# vr42-revB-kbd.net
KiCad netlist of a schematic drawn in EAGLE
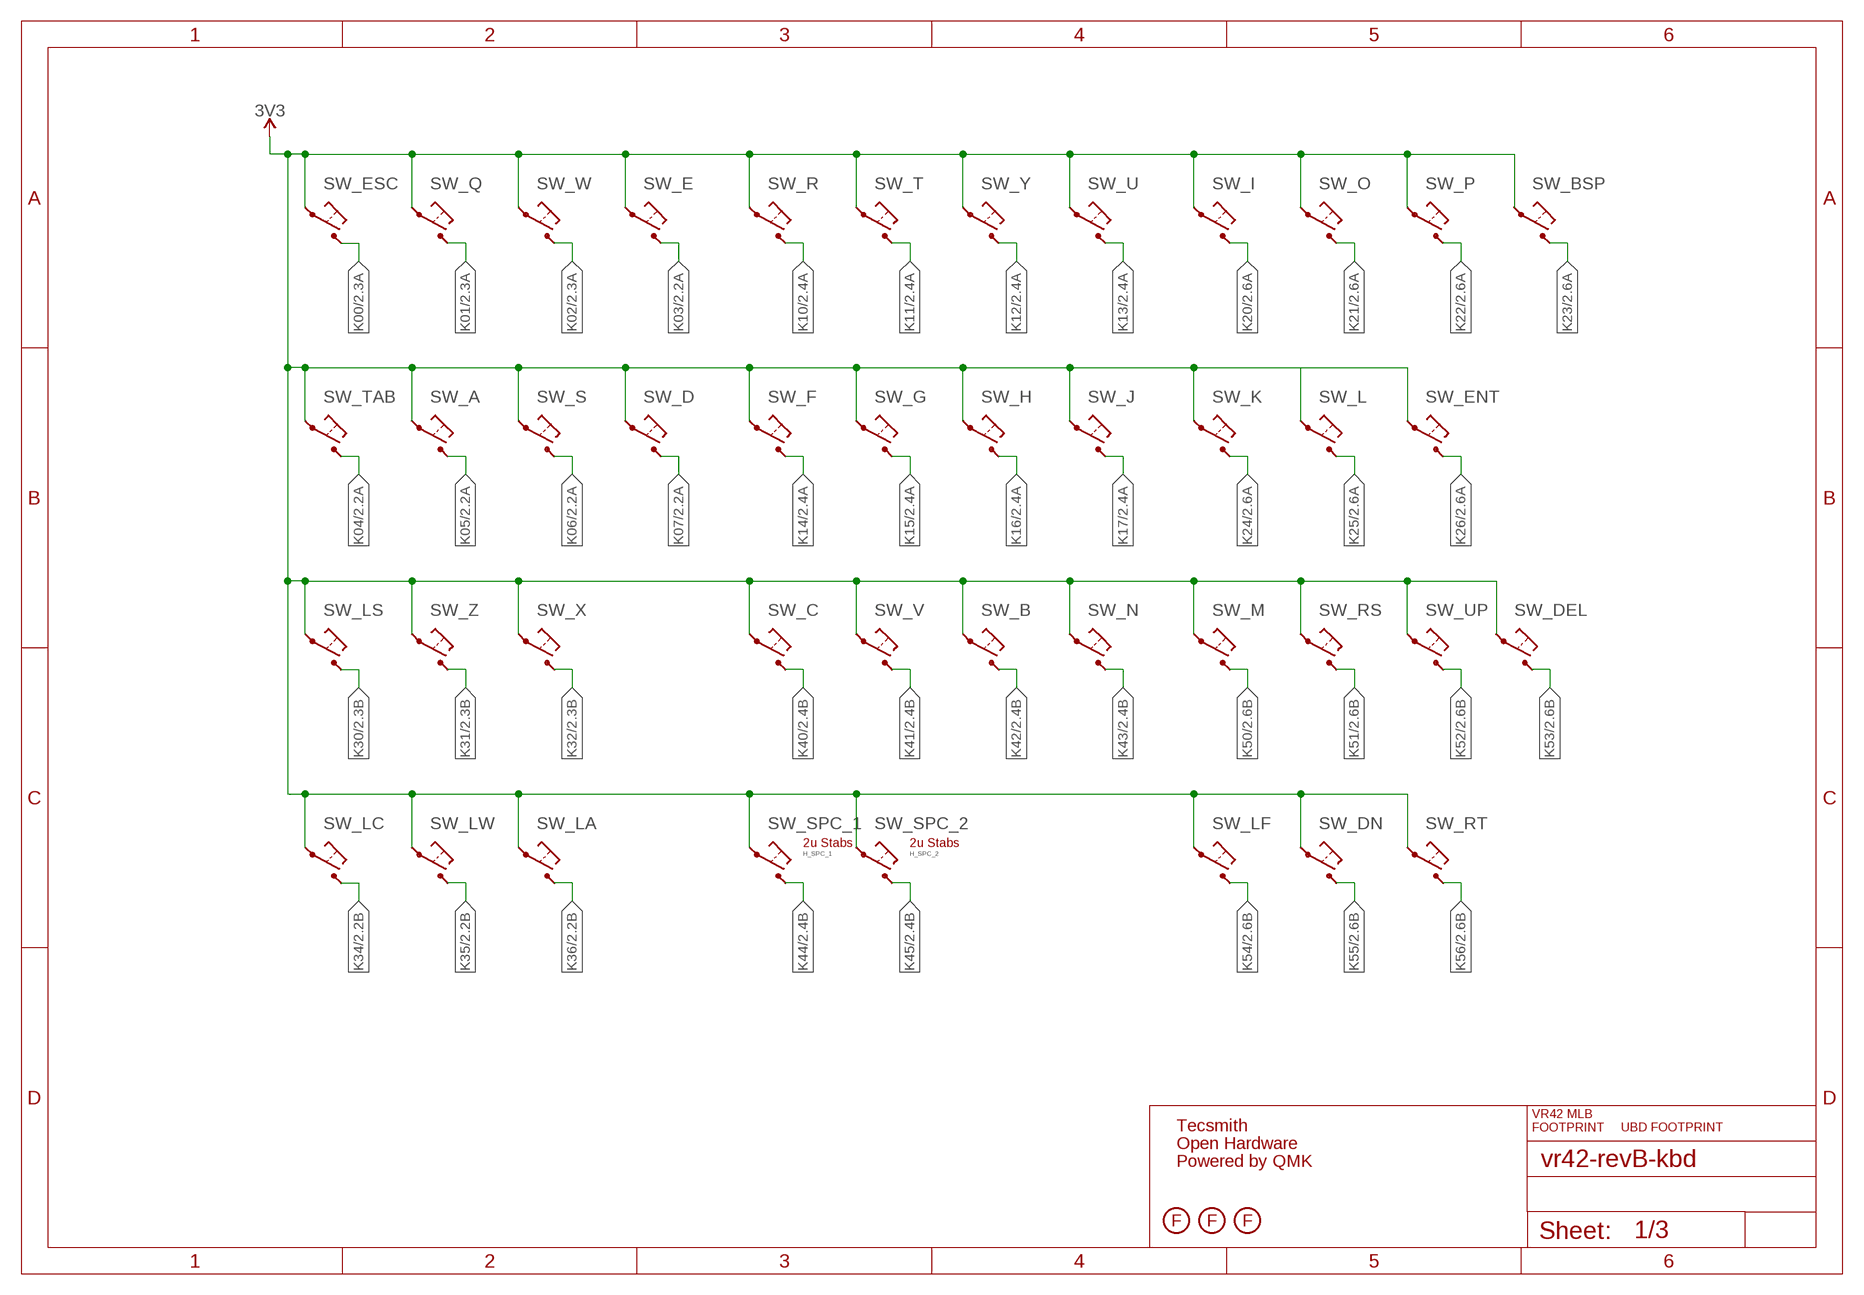
[diagram p0: schematic, sheet 1]
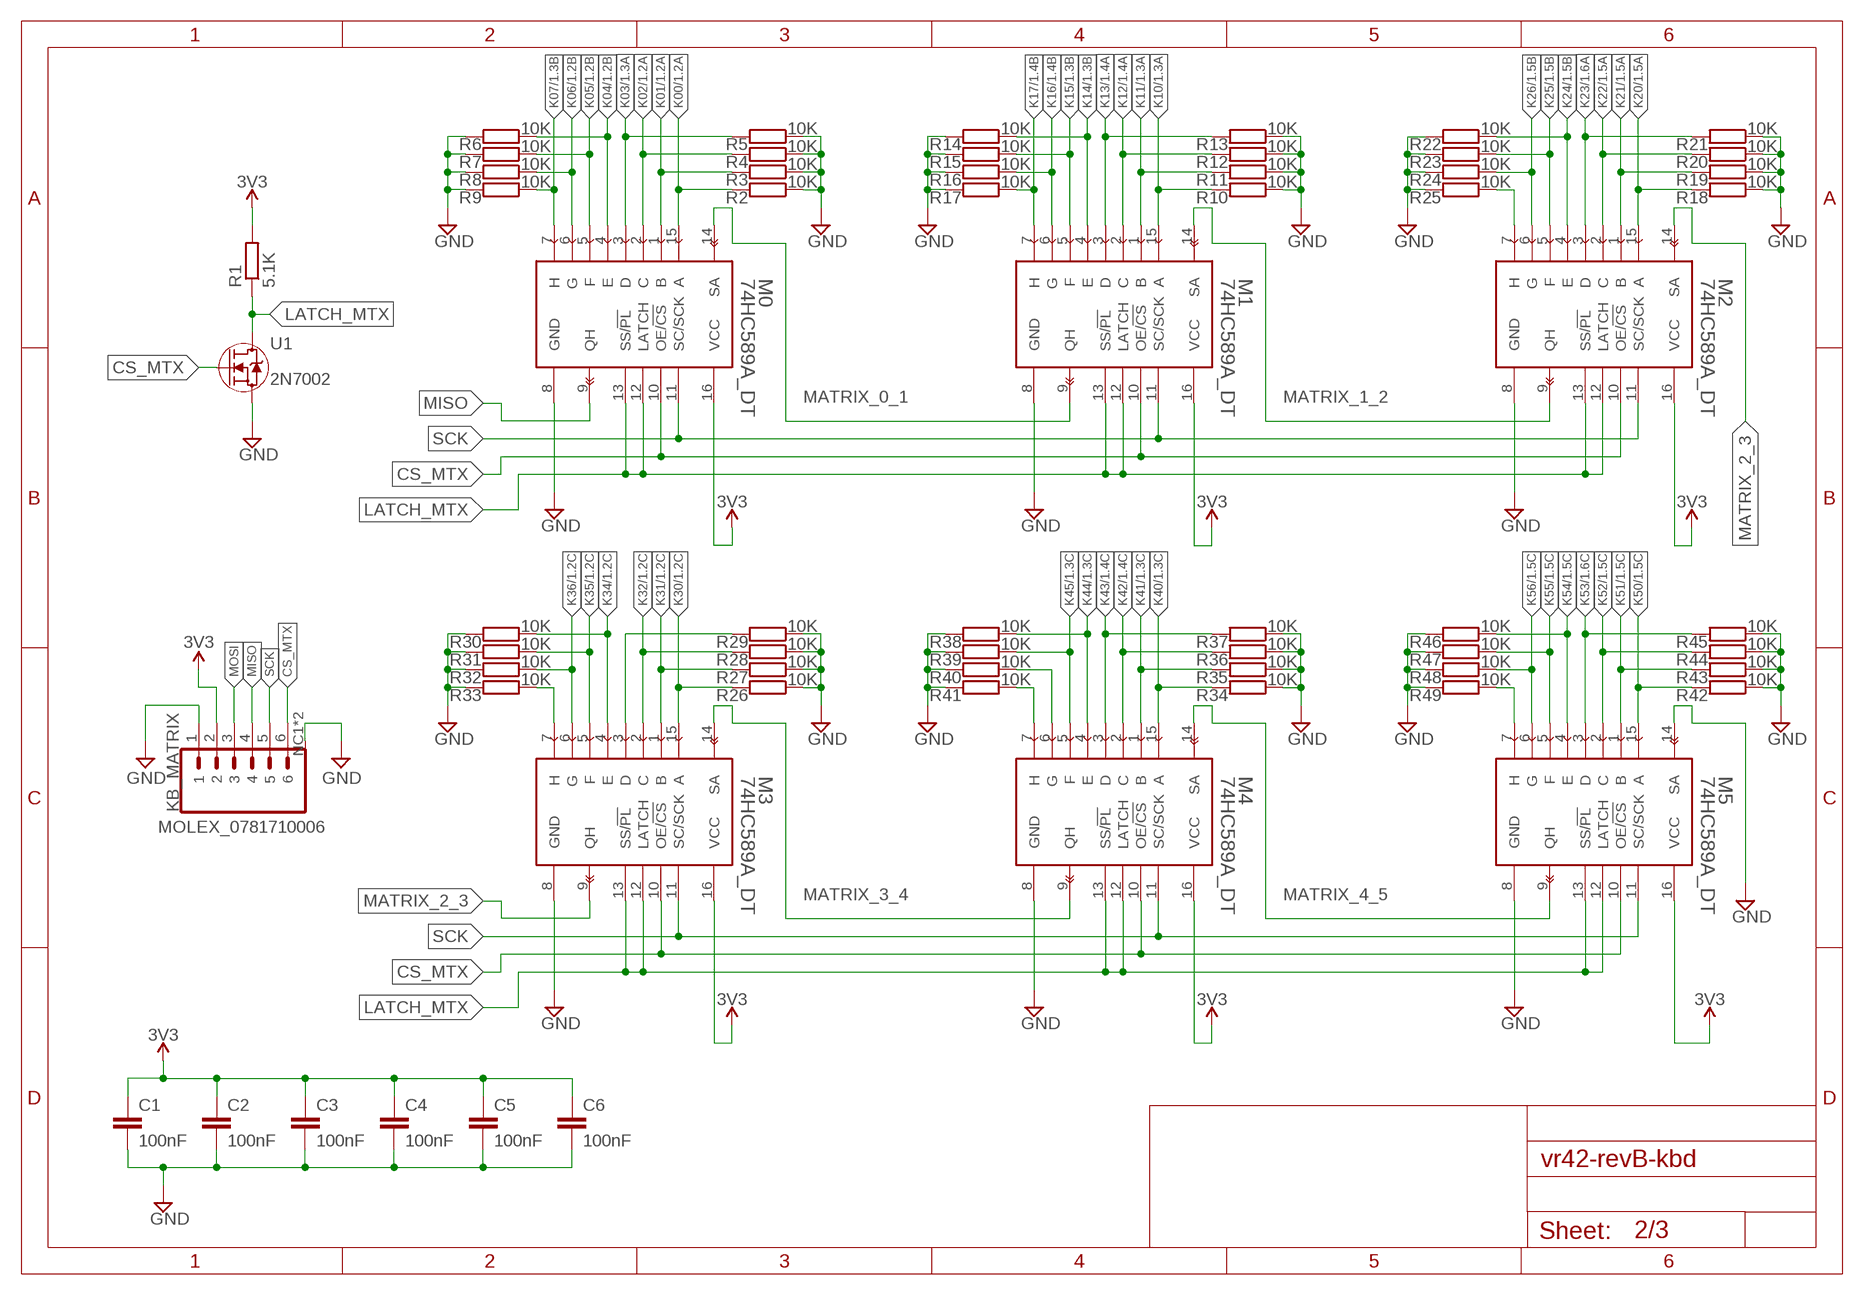
[diagram p1: schematic, sheet 2]
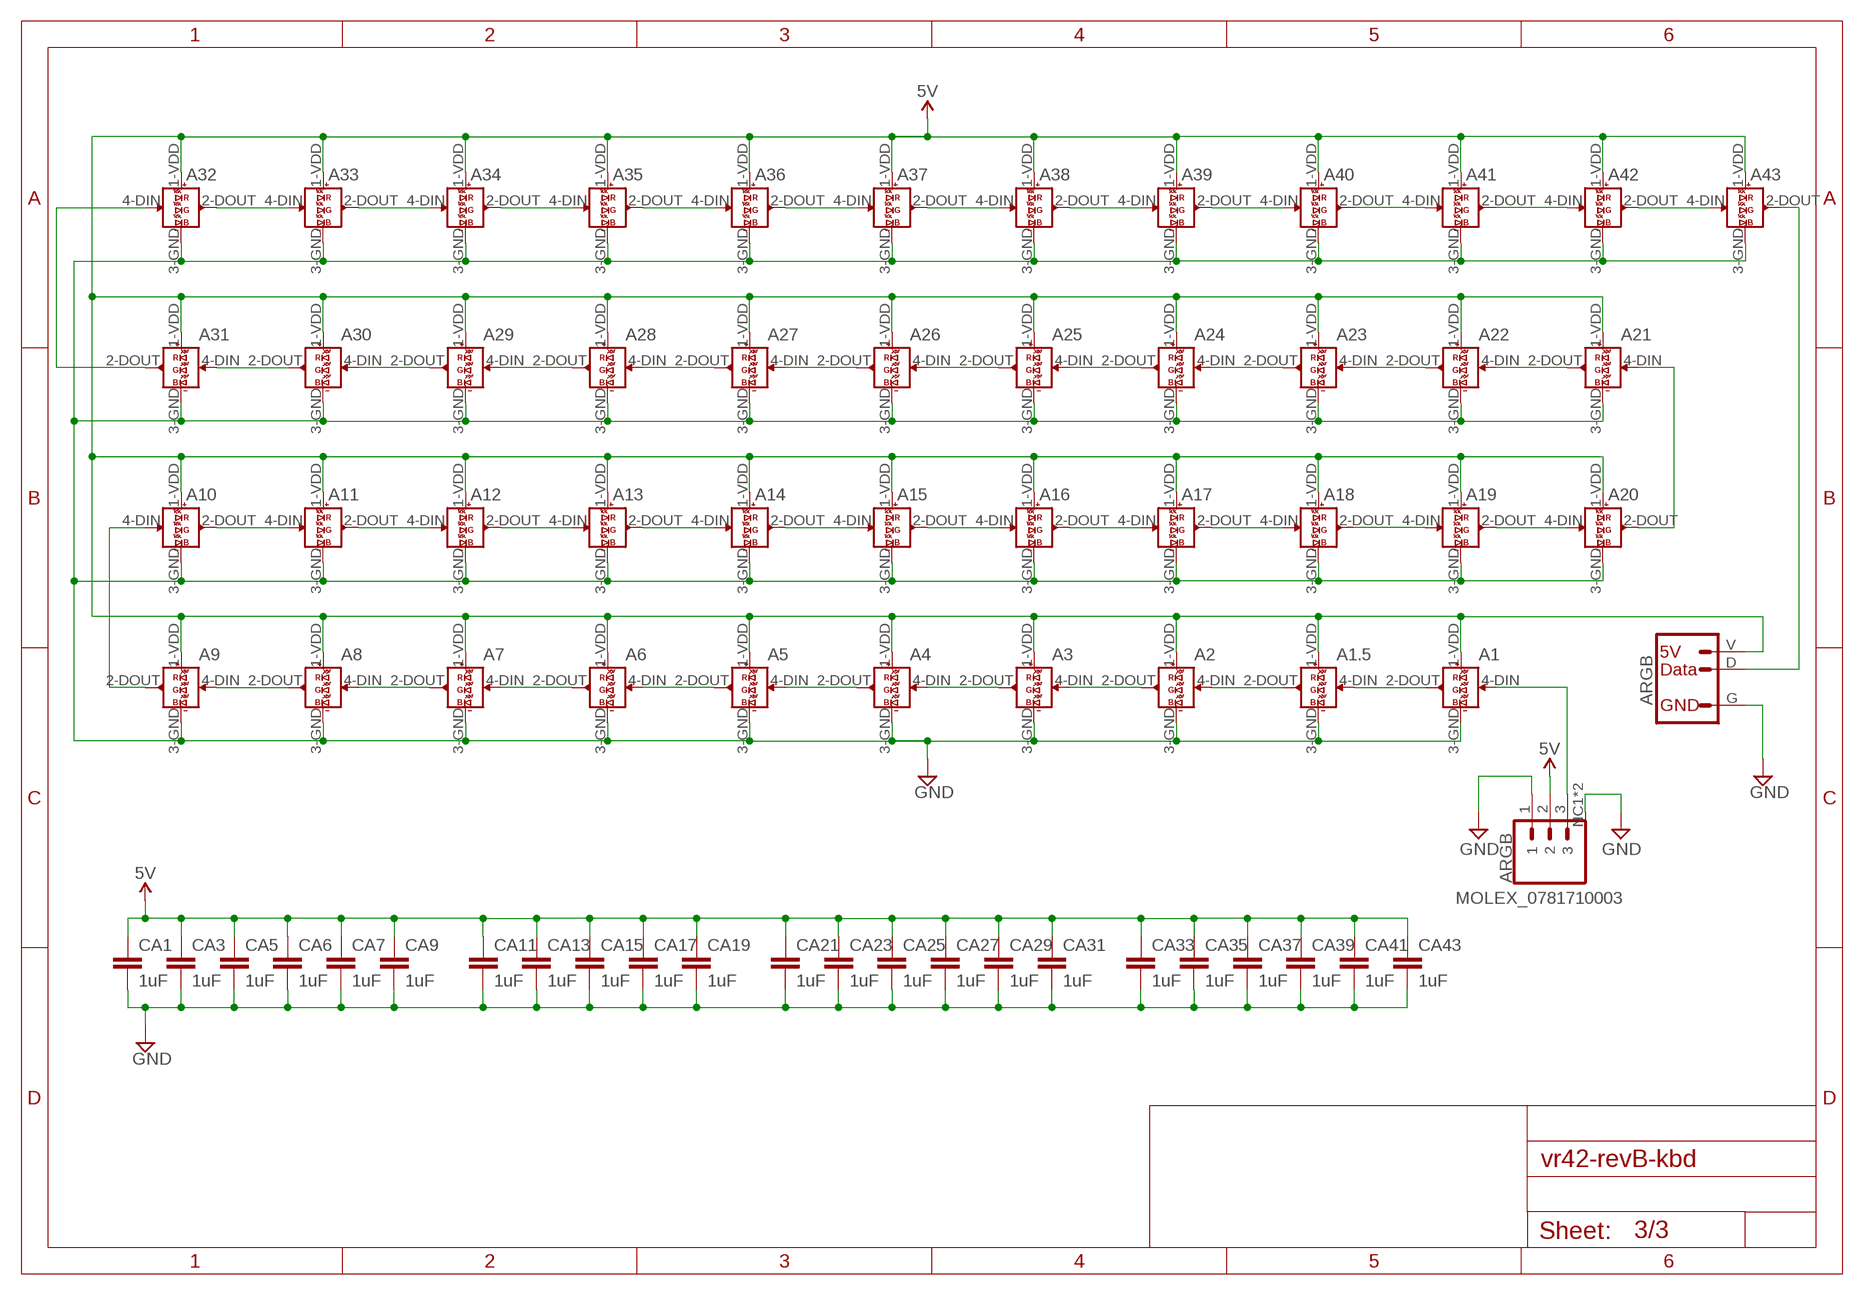
[diagram p2: schematic, sheet 3]

(export (version "E")
  (design (tool "Eeschema 10.0.6"))
  (components
    (comp (ref "A1")
      (value "SK6812-E-REVERSE_V2")
      (footprint "eagle-import:SK6812-E-MILL_V2")
      (libsource (lib "eagle-import") (part "SK6812-E-REVERSE_V2"))
    )
    (comp (ref "A1.5")
      (value "SK6812-E-REVERSE_V2")
      (footprint "eagle-import:SK6812-E-MILL_V2")
      (libsource (lib "eagle-import") (part "SK6812-E-REVERSE_V2"))
    )
    (comp (ref "A2")
      (value "SK6812-E-REVERSE_V2")
      (footprint "eagle-import:SK6812-E-MILL_V2")
      (libsource (lib "eagle-import") (part "SK6812-E-REVERSE_V2"))
    )
    (comp (ref "A3")
      (value "SK6812-E-REVERSE_V2")
      (footprint "eagle-import:SK6812-E-MILL_V2")
      (libsource (lib "eagle-import") (part "SK6812-E-REVERSE_V2"))
    )
    (comp (ref "A4")
      (value "SK6812-E-REVERSE_V2")
      (footprint "eagle-import:SK6812-E-MILL_V2")
      (libsource (lib "eagle-import") (part "SK6812-E-REVERSE_V2"))
    )
    (comp (ref "A5")
      (value "SK6812-E-REVERSE_V2")
      (footprint "eagle-import:SK6812-E-MILL_V2")
      (libsource (lib "eagle-import") (part "SK6812-E-REVERSE_V2"))
    )
    (comp (ref "A6")
      (value "SK6812-E-REVERSE_V2")
      (footprint "eagle-import:SK6812-E-MILL_V2")
      (libsource (lib "eagle-import") (part "SK6812-E-REVERSE_V2"))
    )
    (comp (ref "A7")
      (value "SK6812-E-REVERSE_V2")
      (footprint "eagle-import:SK6812-E-MILL_V2")
      (libsource (lib "eagle-import") (part "SK6812-E-REVERSE_V2"))
    )
    (comp (ref "A8")
      (value "SK6812-E-REVERSE_V2")
      (footprint "eagle-import:SK6812-E-MILL_V2")
      (libsource (lib "eagle-import") (part "SK6812-E-REVERSE_V2"))
    )
    (comp (ref "A9")
      (value "SK6812-E-REVERSE_V2")
      (footprint "eagle-import:SK6812-E-MILL_V2")
      (libsource (lib "eagle-import") (part "SK6812-E-REVERSE_V2"))
    )
    (comp (ref "A10")
      (value "SK6812-E-REVERSE_V2")
      (footprint "eagle-import:SK6812-E-MILL_V2")
      (libsource (lib "eagle-import") (part "SK6812-E-REVERSE_V2"))
    )
    (comp (ref "A11")
      (value "SK6812-E-REVERSE_V2")
      (footprint "eagle-import:SK6812-E-MILL_V2")
      (libsource (lib "eagle-import") (part "SK6812-E-REVERSE_V2"))
    )
    (comp (ref "A12")
      (value "SK6812-E-REVERSE_V2")
      (footprint "eagle-import:SK6812-E-MILL_V2")
      (libsource (lib "eagle-import") (part "SK6812-E-REVERSE_V2"))
    )
    (comp (ref "A13")
      (value "SK6812-E-REVERSE_V2")
      (footprint "eagle-import:SK6812-E-MILL_V2")
      (libsource (lib "eagle-import") (part "SK6812-E-REVERSE_V2"))
    )
    (comp (ref "A14")
      (value "SK6812-E-REVERSE_V2")
      (footprint "eagle-import:SK6812-E-MILL_V2")
      (libsource (lib "eagle-import") (part "SK6812-E-REVERSE_V2"))
    )
    (comp (ref "A15")
      (value "SK6812-E-REVERSE_V2")
      (footprint "eagle-import:SK6812-E-MILL_V2")
      (libsource (lib "eagle-import") (part "SK6812-E-REVERSE_V2"))
    )
    (comp (ref "A16")
      (value "SK6812-E-REVERSE_V2")
      (footprint "eagle-import:SK6812-E-MILL_V2")
      (libsource (lib "eagle-import") (part "SK6812-E-REVERSE_V2"))
    )
    (comp (ref "A17")
      (value "SK6812-E-REVERSE_V2")
      (footprint "eagle-import:SK6812-E-MILL_V2")
      (libsource (lib "eagle-import") (part "SK6812-E-REVERSE_V2"))
    )
    (comp (ref "A18")
      (value "SK6812-E-REVERSE_V2")
      (footprint "eagle-import:SK6812-E-MILL_V2")
      (libsource (lib "eagle-import") (part "SK6812-E-REVERSE_V2"))
    )
    (comp (ref "A19")
      (value "SK6812-E-REVERSE_V2")
      (footprint "eagle-import:SK6812-E-MILL_V2")
      (libsource (lib "eagle-import") (part "SK6812-E-REVERSE_V2"))
    )
    (comp (ref "A20")
      (value "SK6812-E-REVERSE_V2")
      (footprint "eagle-import:SK6812-E-MILL_V2")
      (libsource (lib "eagle-import") (part "SK6812-E-REVERSE_V2"))
    )
    (comp (ref "A21")
      (value "SK6812-E-REVERSE_V2")
      (footprint "eagle-import:SK6812-E-MILL_V2")
      (libsource (lib "eagle-import") (part "SK6812-E-REVERSE_V2"))
    )
    (comp (ref "A22")
      (value "SK6812-E-REVERSE_V2")
      (footprint "eagle-import:SK6812-E-MILL_V2")
      (libsource (lib "eagle-import") (part "SK6812-E-REVERSE_V2"))
    )
    (comp (ref "A23")
      (value "SK6812-E-REVERSE_V2")
      (footprint "eagle-import:SK6812-E-MILL_V2")
      (libsource (lib "eagle-import") (part "SK6812-E-REVERSE_V2"))
    )
    (comp (ref "A24")
      (value "SK6812-E-REVERSE_V2")
      (footprint "eagle-import:SK6812-E-MILL_V2")
      (libsource (lib "eagle-import") (part "SK6812-E-REVERSE_V2"))
    )
    (comp (ref "A25")
      (value "SK6812-E-REVERSE_V2")
      (footprint "eagle-import:SK6812-E-MILL_V2")
      (libsource (lib "eagle-import") (part "SK6812-E-REVERSE_V2"))
    )
    (comp (ref "A26")
      (value "SK6812-E-REVERSE_V2")
      (footprint "eagle-import:SK6812-E-MILL_V2")
      (libsource (lib "eagle-import") (part "SK6812-E-REVERSE_V2"))
    )
    (comp (ref "A27")
      (value "SK6812-E-REVERSE_V2")
      (footprint "eagle-import:SK6812-E-MILL_V2")
      (libsource (lib "eagle-import") (part "SK6812-E-REVERSE_V2"))
    )
    (comp (ref "A28")
      (value "SK6812-E-REVERSE_V2")
      (footprint "eagle-import:SK6812-E-MILL_V2")
      (libsource (lib "eagle-import") (part "SK6812-E-REVERSE_V2"))
    )
    (comp (ref "A29")
      (value "SK6812-E-REVERSE_V2")
      (footprint "eagle-import:SK6812-E-MILL_V2")
      (libsource (lib "eagle-import") (part "SK6812-E-REVERSE_V2"))
    )
    (comp (ref "A30")
      (value "SK6812-E-REVERSE_V2")
      (footprint "eagle-import:SK6812-E-MILL_V2")
      (libsource (lib "eagle-import") (part "SK6812-E-REVERSE_V2"))
    )
    (comp (ref "A31")
      (value "SK6812-E-REVERSE_V2")
      (footprint "eagle-import:SK6812-E-MILL_V2")
      (libsource (lib "eagle-import") (part "SK6812-E-REVERSE_V2"))
    )
    (comp (ref "A32")
      (value "SK6812-E-REVERSE_V2")
      (footprint "eagle-import:SK6812-E-MILL_V2")
      (libsource (lib "eagle-import") (part "SK6812-E-REVERSE_V2"))
    )
    (comp (ref "A33")
      (value "SK6812-E-REVERSE_V2")
      (footprint "eagle-import:SK6812-E-MILL_V2")
      (libsource (lib "eagle-import") (part "SK6812-E-REVERSE_V2"))
    )
    (comp (ref "A34")
      (value "SK6812-E-REVERSE_V2")
      (footprint "eagle-import:SK6812-E-MILL_V2")
      (libsource (lib "eagle-import") (part "SK6812-E-REVERSE_V2"))
    )
    (comp (ref "A35")
      (value "SK6812-E-REVERSE_V2")
      (footprint "eagle-import:SK6812-E-MILL_V2")
      (libsource (lib "eagle-import") (part "SK6812-E-REVERSE_V2"))
    )
    (comp (ref "A36")
      (value "SK6812-E-REVERSE_V2")
      (footprint "eagle-import:SK6812-E-MILL_V2")
      (libsource (lib "eagle-import") (part "SK6812-E-REVERSE_V2"))
    )
    (comp (ref "A37")
      (value "SK6812-E-REVERSE_V2")
      (footprint "eagle-import:SK6812-E-MILL_V2")
      (libsource (lib "eagle-import") (part "SK6812-E-REVERSE_V2"))
    )
    (comp (ref "A38")
      (value "SK6812-E-REVERSE_V2")
      (footprint "eagle-import:SK6812-E-MILL_V2")
      (libsource (lib "eagle-import") (part "SK6812-E-REVERSE_V2"))
    )
    (comp (ref "A39")
      (value "SK6812-E-REVERSE_V2")
      (footprint "eagle-import:SK6812-E-MILL_V2")
      (libsource (lib "eagle-import") (part "SK6812-E-REVERSE_V2"))
    )
    (comp (ref "A40")
      (value "SK6812-E-REVERSE_V2")
      (footprint "eagle-import:SK6812-E-MILL_V2")
      (libsource (lib "eagle-import") (part "SK6812-E-REVERSE_V2"))
    )
    (comp (ref "A41")
      (value "SK6812-E-REVERSE_V2")
      (footprint "eagle-import:SK6812-E-MILL_V2")
      (libsource (lib "eagle-import") (part "SK6812-E-REVERSE_V2"))
    )
    (comp (ref "A42")
      (value "SK6812-E-REVERSE_V2")
      (footprint "eagle-import:SK6812-E-MILL_V2")
      (libsource (lib "eagle-import") (part "SK6812-E-REVERSE_V2"))
    )
    (comp (ref "A43")
      (value "SK6812-E-REVERSE_V2")
      (footprint "eagle-import:SK6812-E-MILL_V2")
      (libsource (lib "eagle-import") (part "SK6812-E-REVERSE_V2"))
    )
    (comp (ref "ARGB")
      (value "MOLEX_0781710003")
      (footprint "eagle-import:MOLEX_781710003")
      (libsource (lib "eagle-import") (part "MOLEX_0781710003"))
    )
    (comp (ref "CA1")
      (value "1uF")
      (footprint "eagle-import:C0603")
      (libsource (lib "eagle-import") (part "C-EUC0603"))
    )
    (comp (ref "CA3")
      (value "1uF")
      (footprint "eagle-import:C0603")
      (libsource (lib "eagle-import") (part "C-EUC0603"))
    )
    (comp (ref "CA5")
      (value "1uF")
      (footprint "eagle-import:C0603")
      (libsource (lib "eagle-import") (part "C-EUC0603"))
    )
    (comp (ref "CA6")
      (value "1uF")
      (footprint "eagle-import:C0603")
      (libsource (lib "eagle-import") (part "C-EUC0603"))
    )
    (comp (ref "CA7")
      (value "1uF")
      (footprint "eagle-import:C0603")
      (libsource (lib "eagle-import") (part "C-EUC0603"))
    )
    (comp (ref "CA9")
      (value "1uF")
      (footprint "eagle-import:C0603")
      (libsource (lib "eagle-import") (part "C-EUC0603"))
    )
    (comp (ref "CA11")
      (value "1uF")
      (footprint "eagle-import:C0603")
      (libsource (lib "eagle-import") (part "C-EUC0603"))
    )
    (comp (ref "CA13")
      (value "1uF")
      (footprint "eagle-import:C0603")
      (libsource (lib "eagle-import") (part "C-EUC0603"))
    )
    (comp (ref "CA15")
      (value "1uF")
      (footprint "eagle-import:C0603")
      (libsource (lib "eagle-import") (part "C-EUC0603"))
    )
    (comp (ref "CA17")
      (value "1uF")
      (footprint "eagle-import:C0603")
      (libsource (lib "eagle-import") (part "C-EUC0603"))
    )
    (comp (ref "CA19")
      (value "1uF")
      (footprint "eagle-import:C0603")
      (libsource (lib "eagle-import") (part "C-EUC0603"))
    )
    (comp (ref "CA21")
      (value "1uF")
      (footprint "eagle-import:C0603")
      (libsource (lib "eagle-import") (part "C-EUC0603"))
    )
    (comp (ref "CA23")
      (value "1uF")
      (footprint "eagle-import:C0603")
      (libsource (lib "eagle-import") (part "C-EUC0603"))
    )
    (comp (ref "CA25")
      (value "1uF")
      (footprint "eagle-import:C0603")
      (libsource (lib "eagle-import") (part "C-EUC0603"))
    )
    (comp (ref "CA27")
      (value "1uF")
      (footprint "eagle-import:C0603")
      (libsource (lib "eagle-import") (part "C-EUC0603"))
    )
    (comp (ref "CA29")
      (value "1uF")
      (footprint "eagle-import:C0603")
      (libsource (lib "eagle-import") (part "C-EUC0603"))
    )
    (comp (ref "CA31")
      (value "1uF")
      (footprint "eagle-import:C0603")
      (libsource (lib "eagle-import") (part "C-EUC0603"))
    )
    (comp (ref "CA33")
      (value "1uF")
      (footprint "eagle-import:C0603")
      (libsource (lib "eagle-import") (part "C-EUC0603"))
    )
    (comp (ref "CA35")
      (value "1uF")
      (footprint "eagle-import:C0603")
      (libsource (lib "eagle-import") (part "C-EUC0603"))
    )
    (comp (ref "CA37")
      (value "1uF")
      (footprint "eagle-import:C0603")
      (libsource (lib "eagle-import") (part "C-EUC0603"))
    )
    (comp (ref "CA39")
      (value "1uF")
      (footprint "eagle-import:C0603")
      (libsource (lib "eagle-import") (part "C-EUC0603"))
    )
    (comp (ref "CA41")
      (value "1uF")
      (footprint "eagle-import:C0603")
      (libsource (lib "eagle-import") (part "C-EUC0603"))
    )
    (comp (ref "CA43")
      (value "1uF")
      (footprint "eagle-import:C0603")
      (libsource (lib "eagle-import") (part "C-EUC0603"))
    )
    (comp (ref "I44")
      (value "ARGB")
      (footprint "eagle-import:ARGB")
      (libsource (lib "eagle-import") (part "ARGB"))
    )
    (comp (ref "C1")
      (value "100nF")
      (footprint "eagle-import:C0603")
      (libsource (lib "eagle-import") (part "C-EUC0603"))
    )
    (comp (ref "C2")
      (value "100nF")
      (footprint "eagle-import:C0603")
      (libsource (lib "eagle-import") (part "C-EUC0603"))
    )
    (comp (ref "C3")
      (value "100nF")
      (footprint "eagle-import:C0603")
      (libsource (lib "eagle-import") (part "C-EUC0603"))
    )
    (comp (ref "C4")
      (value "100nF")
      (footprint "eagle-import:C0603")
      (libsource (lib "eagle-import") (part "C-EUC0603"))
    )
    (comp (ref "C5")
      (value "100nF")
      (footprint "eagle-import:C0603")
      (libsource (lib "eagle-import") (part "C-EUC0603"))
    )
    (comp (ref "C6")
      (value "100nF")
      (footprint "eagle-import:C0603")
      (libsource (lib "eagle-import") (part "C-EUC0603"))
    )
    (comp (ref "KB_MATRIX")
      (value "MOLEX_0781710006")
      (footprint "eagle-import:MOLEX_781710006")
      (libsource (lib "eagle-import") (part "MOLEX_0781710006"))
    )
    (comp (ref "M0")
      (value "74HC589A_DT")
      (footprint "eagle-import:TSSOP16")
      (libsource (lib "eagle-import") (part "74HC589A_DT"))
    )
    (comp (ref "M1")
      (value "74HC589A_DT")
      (footprint "eagle-import:TSSOP16")
      (libsource (lib "eagle-import") (part "74HC589A_DT"))
    )
    (comp (ref "M2")
      (value "74HC589A_DT")
      (footprint "eagle-import:TSSOP16")
      (libsource (lib "eagle-import") (part "74HC589A_DT"))
    )
    (comp (ref "M3")
      (value "74HC589A_DT")
      (footprint "eagle-import:TSSOP16")
      (libsource (lib "eagle-import") (part "74HC589A_DT"))
    )
    (comp (ref "M4")
      (value "74HC589A_DT")
      (footprint "eagle-import:TSSOP16")
      (libsource (lib "eagle-import") (part "74HC589A_DT"))
    )
    (comp (ref "M5")
      (value "74HC589A_DT")
      (footprint "eagle-import:TSSOP16")
      (libsource (lib "eagle-import") (part "74HC589A_DT"))
    )
    (comp (ref "R1")
      (value "5.1K")
      (footprint "eagle-import:R0603")
      (libsource (lib "eagle-import") (part "R-EU_R0603"))
    )
    (comp (ref "R2")
      (value "10K")
      (footprint "eagle-import:R0603")
      (libsource (lib "eagle-import") (part "R-EU_R0603"))
    )
    (comp (ref "R3")
      (value "10K")
      (footprint "eagle-import:R0603")
      (libsource (lib "eagle-import") (part "R-EU_R0603"))
    )
    (comp (ref "R4")
      (value "10K")
      (footprint "eagle-import:R0603")
      (libsource (lib "eagle-import") (part "R-EU_R0603"))
    )
    (comp (ref "R5")
      (value "10K")
      (footprint "eagle-import:R0603")
      (libsource (lib "eagle-import") (part "R-EU_R0603"))
    )
    (comp (ref "R6")
      (value "10K")
      (footprint "eagle-import:R0603")
      (libsource (lib "eagle-import") (part "R-EU_R0603"))
    )
    (comp (ref "R7")
      (value "10K")
      (footprint "eagle-import:R0603")
      (libsource (lib "eagle-import") (part "R-EU_R0603"))
    )
    (comp (ref "R8")
      (value "10K")
      (footprint "eagle-import:R0603")
      (libsource (lib "eagle-import") (part "R-EU_R0603"))
    )
    (comp (ref "R9")
      (value "10K")
      (footprint "eagle-import:R0603")
      (libsource (lib "eagle-import") (part "R-EU_R0603"))
    )
    (comp (ref "R10")
      (value "10K")
      (footprint "eagle-import:R0603")
      (libsource (lib "eagle-import") (part "R-EU_R0603"))
    )
    (comp (ref "R11")
      (value "10K")
      (footprint "eagle-import:R0603")
      (libsource (lib "eagle-import") (part "R-EU_R0603"))
    )
    (comp (ref "R12")
      (value "10K")
      (footprint "eagle-import:R0603")
      (libsource (lib "eagle-import") (part "R-EU_R0603"))
    )
    (comp (ref "R13")
      (value "10K")
      (footprint "eagle-import:R0603")
      (libsource (lib "eagle-import") (part "R-EU_R0603"))
    )
    (comp (ref "R14")
      (value "10K")
      (footprint "eagle-import:R0603")
      (libsource (lib "eagle-import") (part "R-EU_R0603"))
    )
    (comp (ref "R15")
      (value "10K")
      (footprint "eagle-import:R0603")
      (libsource (lib "eagle-import") (part "R-EU_R0603"))
    )
    (comp (ref "R16")
      (value "10K")
      (footprint "eagle-import:R0603")
      (libsource (lib "eagle-import") (part "R-EU_R0603"))
    )
    (comp (ref "R17")
      (value "10K")
      (footprint "eagle-import:R0603")
      (libsource (lib "eagle-import") (part "R-EU_R0603"))
    )
    (comp (ref "R18")
      (value "10K")
      (footprint "eagle-import:R0603")
      (libsource (lib "eagle-import") (part "R-EU_R0603"))
    )
    (comp (ref "R19")
      (value "10K")
      (footprint "eagle-import:R0603")
      (libsource (lib "eagle-import") (part "R-EU_R0603"))
    )
    (comp (ref "R20")
      (value "10K")
      (footprint "eagle-import:R0603")
      (libsource (lib "eagle-import") (part "R-EU_R0603"))
    )
    (comp (ref "R21")
      (value "10K")
      (footprint "eagle-import:R0603")
      (libsource (lib "eagle-import") (part "R-EU_R0603"))
    )
    (comp (ref "R22")
      (value "10K")
      (footprint "eagle-import:R0603")
      (libsource (lib "eagle-import") (part "R-EU_R0603"))
    )
    (comp (ref "R23")
      (value "10K")
      (footprint "eagle-import:R0603")
      (libsource (lib "eagle-import") (part "R-EU_R0603"))
    )
    (comp (ref "R24")
      (value "10K")
      (footprint "eagle-import:R0603")
      (libsource (lib "eagle-import") (part "R-EU_R0603"))
    )
    (comp (ref "R25")
      (value "10K")
      (footprint "eagle-import:R0603")
      (libsource (lib "eagle-import") (part "R-EU_R0603"))
    )
    (comp (ref "R26")
      (value "10K")
      (footprint "eagle-import:R0603")
      (libsource (lib "eagle-import") (part "R-EU_R0603"))
    )
    (comp (ref "R27")
      (value "10K")
      (footprint "eagle-import:R0603")
      (libsource (lib "eagle-import") (part "R-EU_R0603"))
    )
    (comp (ref "R28")
      (value "10K")
      (footprint "eagle-import:R0603")
      (libsource (lib "eagle-import") (part "R-EU_R0603"))
    )
    (comp (ref "R29")
      (value "10K")
      (footprint "eagle-import:R0603")
      (libsource (lib "eagle-import") (part "R-EU_R0603"))
    )
    (comp (ref "R30")
      (value "10K")
      (footprint "eagle-import:R0603")
      (libsource (lib "eagle-import") (part "R-EU_R0603"))
    )
    (comp (ref "R31")
      (value "10K")
      (footprint "eagle-import:R0603")
      (libsource (lib "eagle-import") (part "R-EU_R0603"))
    )
    (comp (ref "R32")
      (value "10K")
      (footprint "eagle-import:R0603")
      (libsource (lib "eagle-import") (part "R-EU_R0603"))
    )
    (comp (ref "R33")
      (value "10K")
      (footprint "eagle-import:R0603")
      (libsource (lib "eagle-import") (part "R-EU_R0603"))
    )
    (comp (ref "R34")
      (value "10K")
      (footprint "eagle-import:R0603")
      (libsource (lib "eagle-import") (part "R-EU_R0603"))
    )
    (comp (ref "R35")
      (value "10K")
      (footprint "eagle-import:R0603")
      (libsource (lib "eagle-import") (part "R-EU_R0603"))
    )
    (comp (ref "R36")
      (value "10K")
      (footprint "eagle-import:R0603")
      (libsource (lib "eagle-import") (part "R-EU_R0603"))
    )
    (comp (ref "R37")
      (value "10K")
      (footprint "eagle-import:R0603")
      (libsource (lib "eagle-import") (part "R-EU_R0603"))
    )
    (comp (ref "R38")
      (value "10K")
      (footprint "eagle-import:R0603")
      (libsource (lib "eagle-import") (part "R-EU_R0603"))
    )
    (comp (ref "R39")
      (value "10K")
      (footprint "eagle-import:R0603")
      (libsource (lib "eagle-import") (part "R-EU_R0603"))
    )
    (comp (ref "R40")
      (value "10K")
      (footprint "eagle-import:R0603")
      (libsource (lib "eagle-import") (part "R-EU_R0603"))
    )
    (comp (ref "R41")
      (value "10K")
      (footprint "eagle-import:R0603")
      (libsource (lib "eagle-import") (part "R-EU_R0603"))
    )
    (comp (ref "R42")
      (value "10K")
      (footprint "eagle-import:R0603")
      (libsource (lib "eagle-import") (part "R-EU_R0603"))
    )
    (comp (ref "R43")
      (value "10K")
      (footprint "eagle-import:R0603")
      (libsource (lib "eagle-import") (part "R-EU_R0603"))
    )
    (comp (ref "R44")
      (value "10K")
      (footprint "eagle-import:R0603")
      (libsource (lib "eagle-import") (part "R-EU_R0603"))
    )
    (comp (ref "R45")
      (value "10K")
      (footprint "eagle-import:R0603")
      (libsource (lib "eagle-import") (part "R-EU_R0603"))
    )
    (comp (ref "R46")
      (value "10K")
      (footprint "eagle-import:R0603")
      (libsource (lib "eagle-import") (part "R-EU_R0603"))
    )
    (comp (ref "R47")
      (value "10K")
      (footprint "eagle-import:R0603")
      (libsource (lib "eagle-import") (part "R-EU_R0603"))
    )
    (comp (ref "R48")
      (value "10K")
      (footprint "eagle-import:R0603")
      (libsource (lib "eagle-import") (part "R-EU_R0603"))
    )
    (comp (ref "R49")
      (value "10K")
      (footprint "eagle-import:R0603")
      (libsource (lib "eagle-import") (part "R-EU_R0603"))
    )
    (comp (ref "U1")
      (value "2N7002")
      (footprint "eagle-import:TO-236AB_NEX")
      (fields
        (field (name "MANUFACTURER_PART_NUMBER") "2N7002,215")
        (field (name "COPYRIGHT") "Copyright (C) 2024 Ultra Librarian. All rights reserved.")
      )
      (libsource (lib "eagle-import") (part "2N7002"))
    )
    (comp (ref "H_SPC_1")
      (value "MX-STABS-200U")
      (footprint "eagle-import:MX-STABS-200U")
      (libsource (lib "eagle-import") (part "MX-STABS-200U"))
    )
    (comp (ref "H_SPC_2")
      (value "MX-STABS-200U")
      (footprint "eagle-import:MX-STABS-200U")
      (libsource (lib "eagle-import") (part "MX-STABS-200U"))
    )
    (comp (ref "LOGO1")
      (value "OSHW-LOGOL")
      (footprint "eagle-import:OSHW-LOGO-L")
      (libsource (lib "eagle-import") (part "OSHW-LOGOL"))
    )
    (comp (ref "SW_A")
      (value "MX-5-PIN-HOTSWAP-PAD")
      (footprint "eagle-import:MX-5-PIN-HOTSWAP-PAD")
      (libsource (lib "eagle-import") (part "MX-5-PIN-HOTSWAP-PAD"))
    )
    (comp (ref "SW_B")
      (value "MX-5-PIN-HOTSWAP-PAD")
      (footprint "eagle-import:MX-5-PIN-HOTSWAP-PAD")
      (libsource (lib "eagle-import") (part "MX-5-PIN-HOTSWAP-PAD"))
    )
    (comp (ref "SW_BSP")
      (value "MX-5-PIN-HOTSWAP-PAD")
      (footprint "eagle-import:MX-5-PIN-HOTSWAP-PAD")
      (libsource (lib "eagle-import") (part "MX-5-PIN-HOTSWAP-PAD"))
    )
    (comp (ref "SW_C")
      (value "MX-5-PIN-HOTSWAP-PAD")
      (footprint "eagle-import:MX-5-PIN-HOTSWAP-PAD")
      (libsource (lib "eagle-import") (part "MX-5-PIN-HOTSWAP-PAD"))
    )
    (comp (ref "SW_D")
      (value "MX-5-PIN-HOTSWAP-PAD")
      (footprint "eagle-import:MX-5-PIN-HOTSWAP-PAD")
      (libsource (lib "eagle-import") (part "MX-5-PIN-HOTSWAP-PAD"))
    )
    (comp (ref "SW_DEL")
      (value "MX-5-PIN-HOTSWAP-PAD")
      (footprint "eagle-import:MX-5-PIN-HOTSWAP-PAD")
      (libsource (lib "eagle-import") (part "MX-5-PIN-HOTSWAP-PAD"))
    )
    (comp (ref "SW_DN")
      (value "MX-5-PIN-HOTSWAP-PAD")
      (footprint "eagle-import:MX-5-PIN-HOTSWAP-PAD")
      (libsource (lib "eagle-import") (part "MX-5-PIN-HOTSWAP-PAD"))
    )
    (comp (ref "SW_E")
      (value "MX-5-PIN-HOTSWAP-PAD")
      (footprint "eagle-import:MX-5-PIN-HOTSWAP-PAD")
      (libsource (lib "eagle-import") (part "MX-5-PIN-HOTSWAP-PAD"))
    )
    (comp (ref "SW_ENT")
      (value "MX-5-PIN-HOTSWAP-PAD")
      (footprint "eagle-import:MX-5-PIN-HOTSWAP-PAD")
      (libsource (lib "eagle-import") (part "MX-5-PIN-HOTSWAP-PAD"))
    )
    (comp (ref "SW_ESC")
      (value "MX-5-PIN-HOTSWAP-PAD")
      (footprint "eagle-import:MX-5-PIN-HOTSWAP-PAD")
      (libsource (lib "eagle-import") (part "MX-5-PIN-HOTSWAP-PAD"))
    )
    (comp (ref "SW_F")
      (value "MX-5-PIN-HOTSWAP-PAD")
      (footprint "eagle-import:MX-5-PIN-HOTSWAP-PAD")
      (libsource (lib "eagle-import") (part "MX-5-PIN-HOTSWAP-PAD"))
    )
    (comp (ref "SW_G")
      (value "MX-5-PIN-HOTSWAP-PAD")
      (footprint "eagle-import:MX-5-PIN-HOTSWAP-PAD")
      (libsource (lib "eagle-import") (part "MX-5-PIN-HOTSWAP-PAD"))
    )
    (comp (ref "SW_H")
      (value "MX-5-PIN-HOTSWAP-PAD")
      (footprint "eagle-import:MX-5-PIN-HOTSWAP-PAD")
      (libsource (lib "eagle-import") (part "MX-5-PIN-HOTSWAP-PAD"))
    )
    (comp (ref "SW_I")
      (value "MX-5-PIN-HOTSWAP-PAD")
      (footprint "eagle-import:MX-5-PIN-HOTSWAP-PAD")
      (libsource (lib "eagle-import") (part "MX-5-PIN-HOTSWAP-PAD"))
    )
    (comp (ref "SW_J")
      (value "MX-5-PIN-HOTSWAP-PAD")
      (footprint "eagle-import:MX-5-PIN-HOTSWAP-PAD")
      (libsource (lib "eagle-import") (part "MX-5-PIN-HOTSWAP-PAD"))
    )
    (comp (ref "SW_K")
      (value "MX-5-PIN-HOTSWAP-PAD")
      (footprint "eagle-import:MX-5-PIN-HOTSWAP-PAD")
      (libsource (lib "eagle-import") (part "MX-5-PIN-HOTSWAP-PAD"))
    )
    (comp (ref "SW_L")
      (value "MX-5-PIN-HOTSWAP-PAD")
      (footprint "eagle-import:MX-5-PIN-HOTSWAP-PAD")
      (libsource (lib "eagle-import") (part "MX-5-PIN-HOTSWAP-PAD"))
    )
    (comp (ref "SW_LA")
      (value "MX-5-PIN-HOTSWAP-PAD")
      (footprint "eagle-import:MX-5-PIN-HOTSWAP-PAD")
      (libsource (lib "eagle-import") (part "MX-5-PIN-HOTSWAP-PAD"))
    )
    (comp (ref "SW_LC")
      (value "MX-5-PIN-HOTSWAP-PAD")
      (footprint "eagle-import:MX-5-PIN-HOTSWAP-PAD")
      (libsource (lib "eagle-import") (part "MX-5-PIN-HOTSWAP-PAD"))
    )
    (comp (ref "SW_LF")
      (value "MX-5-PIN-HOTSWAP-PAD")
      (footprint "eagle-import:MX-5-PIN-HOTSWAP-PAD")
      (libsource (lib "eagle-import") (part "MX-5-PIN-HOTSWAP-PAD"))
    )
    (comp (ref "SW_LS")
      (value "MX-5-PIN-HOTSWAP-PAD")
      (footprint "eagle-import:MX-5-PIN-HOTSWAP-PAD")
      (libsource (lib "eagle-import") (part "MX-5-PIN-HOTSWAP-PAD"))
    )
    (comp (ref "SW_LW")
      (value "MX-5-PIN-HOTSWAP-PAD")
      (footprint "eagle-import:MX-5-PIN-HOTSWAP-PAD")
      (libsource (lib "eagle-import") (part "MX-5-PIN-HOTSWAP-PAD"))
    )
    (comp (ref "SW_M")
      (value "MX-5-PIN-HOTSWAP-PAD")
      (footprint "eagle-import:MX-5-PIN-HOTSWAP-PAD")
      (libsource (lib "eagle-import") (part "MX-5-PIN-HOTSWAP-PAD"))
    )
    (comp (ref "SW_N")
      (value "MX-5-PIN-HOTSWAP-PAD")
      (footprint "eagle-import:MX-5-PIN-HOTSWAP-PAD")
      (libsource (lib "eagle-import") (part "MX-5-PIN-HOTSWAP-PAD"))
    )
    (comp (ref "SW_O")
      (value "MX-5-PIN-HOTSWAP-PAD")
      (footprint "eagle-import:MX-5-PIN-HOTSWAP-PAD")
      (libsource (lib "eagle-import") (part "MX-5-PIN-HOTSWAP-PAD"))
    )
    (comp (ref "SW_P")
      (value "MX-5-PIN-HOTSWAP-PAD")
      (footprint "eagle-import:MX-5-PIN-HOTSWAP-PAD")
      (libsource (lib "eagle-import") (part "MX-5-PIN-HOTSWAP-PAD"))
    )
    (comp (ref "SW_Q")
      (value "MX-5-PIN-HOTSWAP-PAD")
      (footprint "eagle-import:MX-5-PIN-HOTSWAP-PAD")
      (libsource (lib "eagle-import") (part "MX-5-PIN-HOTSWAP-PAD"))
    )
    (comp (ref "SW_R")
      (value "MX-5-PIN-HOTSWAP-PAD")
      (footprint "eagle-import:MX-5-PIN-HOTSWAP-PAD")
      (libsource (lib "eagle-import") (part "MX-5-PIN-HOTSWAP-PAD"))
    )
    (comp (ref "SW_RS")
      (value "MX-5-PIN-HOTSWAP-PAD")
      (footprint "eagle-import:MX-5-PIN-HOTSWAP-PAD")
      (libsource (lib "eagle-import") (part "MX-5-PIN-HOTSWAP-PAD"))
    )
    (comp (ref "SW_RT")
      (value "MX-5-PIN-HOTSWAP-PAD")
      (footprint "eagle-import:MX-5-PIN-HOTSWAP-PAD")
      (libsource (lib "eagle-import") (part "MX-5-PIN-HOTSWAP-PAD"))
    )
    (comp (ref "SW_S")
      (value "MX-5-PIN-HOTSWAP-PAD")
      (footprint "eagle-import:MX-5-PIN-HOTSWAP-PAD")
      (libsource (lib "eagle-import") (part "MX-5-PIN-HOTSWAP-PAD"))
    )
    (comp (ref "SW_SPC_1")
      (value "MX-5-PIN-HOTSWAP-PAD")
      (footprint "eagle-import:MX-5-PIN-HOTSWAP-PAD")
      (libsource (lib "eagle-import") (part "MX-5-PIN-HOTSWAP-PAD"))
    )
    (comp (ref "SW_SPC_2")
      (value "MX-5-PIN-HOTSWAP-PAD")
      (footprint "eagle-import:MX-5-PIN-HOTSWAP-PAD")
      (libsource (lib "eagle-import") (part "MX-5-PIN-HOTSWAP-PAD"))
    )
    (comp (ref "SW_T")
      (value "MX-5-PIN-HOTSWAP-PAD")
      (footprint "eagle-import:MX-5-PIN-HOTSWAP-PAD")
      (libsource (lib "eagle-import") (part "MX-5-PIN-HOTSWAP-PAD"))
    )
    (comp (ref "SW_TAB")
      (value "MX-5-PIN-HOTSWAP-PAD")
      (footprint "eagle-import:MX-5-PIN-HOTSWAP-PAD")
      (libsource (lib "eagle-import") (part "MX-5-PIN-HOTSWAP-PAD"))
    )
    (comp (ref "SW_U")
      (value "MX-5-PIN-HOTSWAP-PAD")
      (footprint "eagle-import:MX-5-PIN-HOTSWAP-PAD")
      (libsource (lib "eagle-import") (part "MX-5-PIN-HOTSWAP-PAD"))
    )
    (comp (ref "SW_UP")
      (value "MX-5-PIN-HOTSWAP-PAD")
      (footprint "eagle-import:MX-5-PIN-HOTSWAP-PAD")
      (libsource (lib "eagle-import") (part "MX-5-PIN-HOTSWAP-PAD"))
    )
    (comp (ref "SW_V")
      (value "MX-5-PIN-HOTSWAP-PAD")
      (footprint "eagle-import:MX-5-PIN-HOTSWAP-PAD")
      (libsource (lib "eagle-import") (part "MX-5-PIN-HOTSWAP-PAD"))
    )
    (comp (ref "SW_W")
      (value "MX-5-PIN-HOTSWAP-PAD")
      (footprint "eagle-import:MX-5-PIN-HOTSWAP-PAD")
      (libsource (lib "eagle-import") (part "MX-5-PIN-HOTSWAP-PAD"))
    )
    (comp (ref "SW_X")
      (value "MX-5-PIN-HOTSWAP-PAD")
      (footprint "eagle-import:MX-5-PIN-HOTSWAP-PAD")
      (libsource (lib "eagle-import") (part "MX-5-PIN-HOTSWAP-PAD"))
    )
    (comp (ref "SW_Y")
      (value "MX-5-PIN-HOTSWAP-PAD")
      (footprint "eagle-import:MX-5-PIN-HOTSWAP-PAD")
      (libsource (lib "eagle-import") (part "MX-5-PIN-HOTSWAP-PAD"))
    )
    (comp (ref "SW_Z")
      (value "MX-5-PIN-HOTSWAP-PAD")
      (footprint "eagle-import:MX-5-PIN-HOTSWAP-PAD")
      (libsource (lib "eagle-import") (part "MX-5-PIN-HOTSWAP-PAD"))
    )
    (comp (ref "U$1")
      (value "VR42_MLB_FOOTPRINT")
      (footprint "eagle-import:VR42_MLB_FOOTPRINT")
      (libsource (lib "eagle-import") (part "VR42_MLB_FOOTPRINT"))
    )
    (comp (ref "U$2")
      (value "UBD_FOOTPRINT")
      (footprint "eagle-import:UDB_FOOTPRINT")
      (libsource (lib "eagle-import") (part "UBD_FOOTPRINT"))
    )
    (comp (ref "U$3")
      (value "TECSMITH-LOGOLONG")
      (footprint "eagle-import:TECSMITH-NAME")
      (libsource (lib "eagle-import") (part "TECSMITH-LOGOLONG"))
    )
    (comp (ref "U$4")
      (value "QMK_LOGO")
      (footprint "eagle-import:QMK_LOGO")
      (libsource (lib "eagle-import") (part "QMK_LOGO"))
    )
    (comp (ref "U$5")
      (value "FIDUCIAL")
      (footprint "eagle-import:FIDUCIAL")
      (libsource (lib "eagle-import") (part "FIDUCIAL"))
    )
    (comp (ref "U$6")
      (value "FIDUCIAL")
      (footprint "eagle-import:FIDUCIAL")
      (libsource (lib "eagle-import") (part "FIDUCIAL"))
    )
    (comp (ref "U$7")
      (value "FIDUCIAL")
      (footprint "eagle-import:FIDUCIAL")
      (libsource (lib "eagle-import") (part "FIDUCIAL"))
    )
  )
  (nets
    (net (code "1") (name "CS_MTX") (class "Default")
      (node (ref "KB_MATRIX") (pin "6") (pinfunction "6_6") (pintype "power_in"))
      (node (ref "M0") (pin "10") (pinfunction "OE/~{CS}_10") (pintype "bidirectional"))
      (node (ref "M1") (pin "10") (pinfunction "OE/~{CS}_10") (pintype "bidirectional"))
      (node (ref "M2") (pin "10") (pinfunction "OE/~{CS}_10") (pintype "bidirectional"))
      (node (ref "M3") (pin "10") (pinfunction "OE/~{CS}_10") (pintype "bidirectional"))
      (node (ref "M4") (pin "10") (pinfunction "OE/~{CS}_10") (pintype "bidirectional"))
      (node (ref "M5") (pin "10") (pinfunction "OE/~{CS}_10") (pintype "bidirectional"))
      (node (ref "U1") (pin "1") (pinfunction "1_1") (pintype "passive"))
    )
    (net (code "2") (name "GND") (class "Default")
      (node (ref "A1") (pin "3-GND") (pinfunction "3_GND_3-GND") (pintype "power_in"))
      (node (ref "A1.5") (pin "3-GND") (pinfunction "3_GND_3-GND") (pintype "power_in"))
      (node (ref "A10") (pin "3-GND") (pinfunction "3_GND_3-GND") (pintype "power_in"))
      (node (ref "A11") (pin "3-GND") (pinfunction "3_GND_3-GND") (pintype "power_in"))
      (node (ref "A12") (pin "3-GND") (pinfunction "3_GND_3-GND") (pintype "power_in"))
      (node (ref "A13") (pin "3-GND") (pinfunction "3_GND_3-GND") (pintype "power_in"))
      (node (ref "A14") (pin "3-GND") (pinfunction "3_GND_3-GND") (pintype "power_in"))
      (node (ref "A15") (pin "3-GND") (pinfunction "3_GND_3-GND") (pintype "power_in"))
      (node (ref "A16") (pin "3-GND") (pinfunction "3_GND_3-GND") (pintype "power_in"))
      (node (ref "A17") (pin "3-GND") (pinfunction "3_GND_3-GND") (pintype "power_in"))
      (node (ref "A18") (pin "3-GND") (pinfunction "3_GND_3-GND") (pintype "power_in"))
      (node (ref "A19") (pin "3-GND") (pinfunction "3_GND_3-GND") (pintype "power_in"))
      (node (ref "A2") (pin "3-GND") (pinfunction "3_GND_3-GND") (pintype "power_in"))
      (node (ref "A20") (pin "3-GND") (pinfunction "3_GND_3-GND") (pintype "power_in"))
      (node (ref "A21") (pin "3-GND") (pinfunction "3_GND_3-GND") (pintype "power_in"))
      (node (ref "A22") (pin "3-GND") (pinfunction "3_GND_3-GND") (pintype "power_in"))
      (node (ref "A23") (pin "3-GND") (pinfunction "3_GND_3-GND") (pintype "power_in"))
      (node (ref "A24") (pin "3-GND") (pinfunction "3_GND_3-GND") (pintype "power_in"))
      (node (ref "A25") (pin "3-GND") (pinfunction "3_GND_3-GND") (pintype "power_in"))
      (node (ref "A26") (pin "3-GND") (pinfunction "3_GND_3-GND") (pintype "power_in"))
      (node (ref "A27") (pin "3-GND") (pinfunction "3_GND_3-GND") (pintype "power_in"))
      (node (ref "A28") (pin "3-GND") (pinfunction "3_GND_3-GND") (pintype "power_in"))
      (node (ref "A29") (pin "3-GND") (pinfunction "3_GND_3-GND") (pintype "power_in"))
      (node (ref "A3") (pin "3-GND") (pinfunction "3_GND_3-GND") (pintype "power_in"))
      (node (ref "A30") (pin "3-GND") (pinfunction "3_GND_3-GND") (pintype "power_in"))
      (node (ref "A31") (pin "3-GND") (pinfunction "3_GND_3-GND") (pintype "power_in"))
      (node (ref "A32") (pin "3-GND") (pinfunction "3_GND_3-GND") (pintype "power_in"))
      (node (ref "A33") (pin "3-GND") (pinfunction "3_GND_3-GND") (pintype "power_in"))
      (node (ref "A34") (pin "3-GND") (pinfunction "3_GND_3-GND") (pintype "power_in"))
      (node (ref "A35") (pin "3-GND") (pinfunction "3_GND_3-GND") (pintype "power_in"))
      (node (ref "A36") (pin "3-GND") (pinfunction "3_GND_3-GND") (pintype "power_in"))
      (node (ref "A37") (pin "3-GND") (pinfunction "3_GND_3-GND") (pintype "power_in"))
      (node (ref "A38") (pin "3-GND") (pinfunction "3_GND_3-GND") (pintype "power_in"))
      (node (ref "A39") (pin "3-GND") (pinfunction "3_GND_3-GND") (pintype "power_in"))
      (node (ref "A4") (pin "3-GND") (pinfunction "3_GND_3-GND") (pintype "power_in"))
      (node (ref "A40") (pin "3-GND") (pinfunction "3_GND_3-GND") (pintype "power_in"))
      (node (ref "A41") (pin "3-GND") (pinfunction "3_GND_3-GND") (pintype "power_in"))
      (node (ref "A42") (pin "3-GND") (pinfunction "3_GND_3-GND") (pintype "power_in"))
      (node (ref "A43") (pin "3-GND") (pinfunction "3_GND_3-GND") (pintype "power_in"))
      (node (ref "A5") (pin "3-GND") (pinfunction "3_GND_3-GND") (pintype "power_in"))
      (node (ref "A6") (pin "3-GND") (pinfunction "3_GND_3-GND") (pintype "power_in"))
      (node (ref "A7") (pin "3-GND") (pinfunction "3_GND_3-GND") (pintype "power_in"))
      (node (ref "A8") (pin "3-GND") (pinfunction "3_GND_3-GND") (pintype "power_in"))
      (node (ref "A9") (pin "3-GND") (pinfunction "3_GND_3-GND") (pintype "power_in"))
      (node (ref "ARGB") (pin "1") (pinfunction "1_1") (pintype "power_in"))
      (node (ref "ARGB") (pin "NC1") (pinfunction "M_NC1") (pintype "bidirectional"))
      (node (ref "ARGB") (pin "NC2") (pinfunction "M_NC2") (pintype "bidirectional"))
      (node (ref "C1") (pin "2") (pinfunction "2_2") (pintype "passive"))
      (node (ref "C2") (pin "2") (pinfunction "2_2") (pintype "passive"))
      (node (ref "C3") (pin "2") (pinfunction "2_2") (pintype "passive"))
      (node (ref "C4") (pin "2") (pinfunction "2_2") (pintype "passive"))
      (node (ref "C5") (pin "2") (pinfunction "2_2") (pintype "passive"))
      (node (ref "C6") (pin "2") (pinfunction "2_2") (pintype "passive"))
      (node (ref "CA1") (pin "2") (pinfunction "2_2") (pintype "passive"))
      (node (ref "CA11") (pin "2") (pinfunction "2_2") (pintype "passive"))
      (node (ref "CA13") (pin "2") (pinfunction "2_2") (pintype "passive"))
      (node (ref "CA15") (pin "2") (pinfunction "2_2") (pintype "passive"))
      (node (ref "CA17") (pin "2") (pinfunction "2_2") (pintype "passive"))
      (node (ref "CA19") (pin "2") (pinfunction "2_2") (pintype "passive"))
      (node (ref "CA21") (pin "2") (pinfunction "2_2") (pintype "passive"))
      (node (ref "CA23") (pin "2") (pinfunction "2_2") (pintype "passive"))
      (node (ref "CA25") (pin "2") (pinfunction "2_2") (pintype "passive"))
      (node (ref "CA27") (pin "2") (pinfunction "2_2") (pintype "passive"))
      (node (ref "CA29") (pin "2") (pinfunction "2_2") (pintype "passive"))
      (node (ref "CA3") (pin "2") (pinfunction "2_2") (pintype "passive"))
      (node (ref "CA31") (pin "2") (pinfunction "2_2") (pintype "passive"))
      (node (ref "CA33") (pin "2") (pinfunction "2_2") (pintype "passive"))
      (node (ref "CA35") (pin "2") (pinfunction "2_2") (pintype "passive"))
      (node (ref "CA37") (pin "2") (pinfunction "2_2") (pintype "passive"))
      (node (ref "CA39") (pin "2") (pinfunction "2_2") (pintype "passive"))
      (node (ref "CA41") (pin "2") (pinfunction "2_2") (pintype "passive"))
      (node (ref "CA43") (pin "2") (pinfunction "2_2") (pintype "passive"))
      (node (ref "CA5") (pin "2") (pinfunction "2_2") (pintype "passive"))
      (node (ref "CA6") (pin "2") (pinfunction "2_2") (pintype "passive"))
      (node (ref "CA7") (pin "2") (pinfunction "2_2") (pintype "passive"))
      (node (ref "CA9") (pin "2") (pinfunction "2_2") (pintype "passive"))
      (node (ref "I44") (pin "G") (pinfunction "G_G") (pintype "power_in"))
      (node (ref "KB_MATRIX") (pin "1") (pinfunction "1_1") (pintype "power_in"))
      (node (ref "KB_MATRIX") (pin "NC1") (pinfunction "M_NC1") (pintype "bidirectional"))
      (node (ref "KB_MATRIX") (pin "NC2") (pinfunction "M_NC2") (pintype "bidirectional"))
      (node (ref "M0") (pin "8") (pinfunction "GND_8") (pintype "bidirectional"))
      (node (ref "M1") (pin "8") (pinfunction "GND_8") (pintype "bidirectional"))
      (node (ref "M2") (pin "8") (pinfunction "GND_8") (pintype "bidirectional"))
      (node (ref "M3") (pin "8") (pinfunction "GND_8") (pintype "bidirectional"))
      (node (ref "M4") (pin "8") (pinfunction "GND_8") (pintype "bidirectional"))
      (node (ref "M5") (pin "14") (pinfunction "SA_14") (pintype "bidirectional"))
      (node (ref "M5") (pin "8") (pinfunction "GND_8") (pintype "bidirectional"))
      (node (ref "R10") (pin "1") (pinfunction "1_1") (pintype "passive"))
      (node (ref "R11") (pin "1") (pinfunction "1_1") (pintype "passive"))
      (node (ref "R12") (pin "1") (pinfunction "1_1") (pintype "passive"))
      (node (ref "R13") (pin "1") (pinfunction "1_1") (pintype "passive"))
      (node (ref "R14") (pin "2") (pinfunction "2_2") (pintype "passive"))
      (node (ref "R15") (pin "2") (pinfunction "2_2") (pintype "passive"))
      (node (ref "R16") (pin "2") (pinfunction "2_2") (pintype "passive"))
      (node (ref "R17") (pin "2") (pinfunction "2_2") (pintype "passive"))
      (node (ref "R18") (pin "1") (pinfunction "1_1") (pintype "passive"))
      (node (ref "R19") (pin "1") (pinfunction "1_1") (pintype "passive"))
      (node (ref "R2") (pin "1") (pinfunction "1_1") (pintype "passive"))
      (node (ref "R20") (pin "1") (pinfunction "1_1") (pintype "passive"))
      (node (ref "R21") (pin "1") (pinfunction "1_1") (pintype "passive"))
      (node (ref "R22") (pin "2") (pinfunction "2_2") (pintype "passive"))
      (node (ref "R23") (pin "2") (pinfunction "2_2") (pintype "passive"))
      (node (ref "R24") (pin "2") (pinfunction "2_2") (pintype "passive"))
      (node (ref "R25") (pin "2") (pinfunction "2_2") (pintype "passive"))
      (node (ref "R26") (pin "1") (pinfunction "1_1") (pintype "passive"))
      (node (ref "R27") (pin "1") (pinfunction "1_1") (pintype "passive"))
      (node (ref "R28") (pin "1") (pinfunction "1_1") (pintype "passive"))
      (node (ref "R29") (pin "1") (pinfunction "1_1") (pintype "passive"))
      (node (ref "R3") (pin "1") (pinfunction "1_1") (pintype "passive"))
      (node (ref "R30") (pin "2") (pinfunction "2_2") (pintype "passive"))
      (node (ref "R31") (pin "2") (pinfunction "2_2") (pintype "passive"))
      (node (ref "R32") (pin "2") (pinfunction "2_2") (pintype "passive"))
      (node (ref "R33") (pin "2") (pinfunction "2_2") (pintype "passive"))
      (node (ref "R34") (pin "1") (pinfunction "1_1") (pintype "passive"))
      (node (ref "R35") (pin "1") (pinfunction "1_1") (pintype "passive"))
      (node (ref "R36") (pin "1") (pinfunction "1_1") (pintype "passive"))
      (node (ref "R37") (pin "1") (pinfunction "1_1") (pintype "passive"))
      (node (ref "R38") (pin "2") (pinfunction "2_2") (pintype "passive"))
      (node (ref "R39") (pin "2") (pinfunction "2_2") (pintype "passive"))
      (node (ref "R4") (pin "1") (pinfunction "1_1") (pintype "passive"))
      (node (ref "R40") (pin "2") (pinfunction "2_2") (pintype "passive"))
      (node (ref "R41") (pin "2") (pinfunction "2_2") (pintype "passive"))
      (node (ref "R42") (pin "1") (pinfunction "1_1") (pintype "passive"))
      (node (ref "R43") (pin "1") (pinfunction "1_1") (pintype "passive"))
      (node (ref "R44") (pin "1") (pinfunction "1_1") (pintype "passive"))
      (node (ref "R45") (pin "1") (pinfunction "1_1") (pintype "passive"))
      (node (ref "R46") (pin "2") (pinfunction "2_2") (pintype "passive"))
      (node (ref "R47") (pin "2") (pinfunction "2_2") (pintype "passive"))
      (node (ref "R48") (pin "2") (pinfunction "2_2") (pintype "passive"))
      (node (ref "R49") (pin "2") (pinfunction "2_2") (pintype "passive"))
      (node (ref "R5") (pin "1") (pinfunction "1_1") (pintype "passive"))
      (node (ref "R6") (pin "2") (pinfunction "2_2") (pintype "passive"))
      (node (ref "R7") (pin "2") (pinfunction "2_2") (pintype "passive"))
      (node (ref "R8") (pin "2") (pinfunction "2_2") (pintype "passive"))
      (node (ref "R9") (pin "2") (pinfunction "2_2") (pintype "passive"))
      (node (ref "U1") (pin "2") (pinfunction "3_2") (pintype "passive"))
    )
    (net (code "3") (name "K00") (class "Default")
      (node (ref "M0") (pin "15") (pinfunction "A_15") (pintype "bidirectional"))
      (node (ref "R2") (pin "2") (pinfunction "2_2") (pintype "passive"))
      (node (ref "SW_ESC") (pin "1@1") (pinfunction "P_1@1") (pintype "passive"))
      (node (ref "SW_ESC") (pin "1@2") (pinfunction "P_1@2") (pintype "passive"))
    )
    (net (code "4") (name "K01") (class "Default")
      (node (ref "M0") (pin "1") (pinfunction "B_1") (pintype "bidirectional"))
      (node (ref "R3") (pin "2") (pinfunction "2_2") (pintype "passive"))
      (node (ref "SW_Q") (pin "1@1") (pinfunction "P_1@1") (pintype "passive"))
      (node (ref "SW_Q") (pin "1@2") (pinfunction "P_1@2") (pintype "passive"))
    )
    (net (code "5") (name "K02") (class "Default")
      (node (ref "M0") (pin "2") (pinfunction "C_2") (pintype "bidirectional"))
      (node (ref "R4") (pin "2") (pinfunction "2_2") (pintype "passive"))
      (node (ref "SW_W") (pin "1@1") (pinfunction "P_1@1") (pintype "passive"))
      (node (ref "SW_W") (pin "1@2") (pinfunction "P_1@2") (pintype "passive"))
    )
    (net (code "6") (name "K03") (class "Default")
      (node (ref "M0") (pin "3") (pinfunction "D_3") (pintype "bidirectional"))
      (node (ref "R5") (pin "2") (pinfunction "2_2") (pintype "passive"))
      (node (ref "SW_E") (pin "1@1") (pinfunction "P_1@1") (pintype "passive"))
      (node (ref "SW_E") (pin "1@2") (pinfunction "P_1@2") (pintype "passive"))
    )
    (net (code "7") (name "K04") (class "Default")
      (node (ref "M0") (pin "4") (pinfunction "E_4") (pintype "bidirectional"))
      (node (ref "R6") (pin "1") (pinfunction "1_1") (pintype "passive"))
      (node (ref "SW_TAB") (pin "1@1") (pinfunction "P_1@1") (pintype "passive"))
      (node (ref "SW_TAB") (pin "1@2") (pinfunction "P_1@2") (pintype "passive"))
    )
    (net (code "8") (name "K05") (class "Default")
      (node (ref "M0") (pin "5") (pinfunction "F_5") (pintype "bidirectional"))
      (node (ref "R7") (pin "1") (pinfunction "1_1") (pintype "passive"))
      (node (ref "SW_A") (pin "1@1") (pinfunction "P_1@1") (pintype "passive"))
      (node (ref "SW_A") (pin "1@2") (pinfunction "P_1@2") (pintype "passive"))
    )
    (net (code "9") (name "K06") (class "Default")
      (node (ref "M0") (pin "6") (pinfunction "G_6") (pintype "bidirectional"))
      (node (ref "R8") (pin "1") (pinfunction "1_1") (pintype "passive"))
      (node (ref "SW_S") (pin "1@1") (pinfunction "P_1@1") (pintype "passive"))
      (node (ref "SW_S") (pin "1@2") (pinfunction "P_1@2") (pintype "passive"))
    )
    (net (code "10") (name "K07") (class "Default")
      (node (ref "M0") (pin "7") (pinfunction "H_7") (pintype "bidirectional"))
      (node (ref "R9") (pin "1") (pinfunction "1_1") (pintype "passive"))
      (node (ref "SW_D") (pin "1@1") (pinfunction "P_1@1") (pintype "passive"))
      (node (ref "SW_D") (pin "1@2") (pinfunction "P_1@2") (pintype "passive"))
    )
    (net (code "11") (name "K10") (class "Default")
      (node (ref "M1") (pin "15") (pinfunction "A_15") (pintype "bidirectional"))
      (node (ref "R10") (pin "2") (pinfunction "2_2") (pintype "passive"))
      (node (ref "SW_R") (pin "1@1") (pinfunction "P_1@1") (pintype "passive"))
      (node (ref "SW_R") (pin "1@2") (pinfunction "P_1@2") (pintype "passive"))
    )
    (net (code "12") (name "K11") (class "Default")
      (node (ref "M1") (pin "1") (pinfunction "B_1") (pintype "bidirectional"))
      (node (ref "R11") (pin "2") (pinfunction "2_2") (pintype "passive"))
      (node (ref "SW_T") (pin "1@1") (pinfunction "P_1@1") (pintype "passive"))
      (node (ref "SW_T") (pin "1@2") (pinfunction "P_1@2") (pintype "passive"))
    )
    (net (code "13") (name "K12") (class "Default")
      (node (ref "M1") (pin "2") (pinfunction "C_2") (pintype "bidirectional"))
      (node (ref "R12") (pin "2") (pinfunction "2_2") (pintype "passive"))
      (node (ref "SW_Y") (pin "1@1") (pinfunction "P_1@1") (pintype "passive"))
      (node (ref "SW_Y") (pin "1@2") (pinfunction "P_1@2") (pintype "passive"))
    )
    (net (code "14") (name "K13") (class "Default")
      (node (ref "M1") (pin "3") (pinfunction "D_3") (pintype "bidirectional"))
      (node (ref "R13") (pin "2") (pinfunction "2_2") (pintype "passive"))
      (node (ref "SW_U") (pin "1@1") (pinfunction "P_1@1") (pintype "passive"))
      (node (ref "SW_U") (pin "1@2") (pinfunction "P_1@2") (pintype "passive"))
    )
    (net (code "15") (name "K14") (class "Default")
      (node (ref "M1") (pin "4") (pinfunction "E_4") (pintype "bidirectional"))
      (node (ref "R14") (pin "1") (pinfunction "1_1") (pintype "passive"))
      (node (ref "SW_F") (pin "1@1") (pinfunction "P_1@1") (pintype "passive"))
      (node (ref "SW_F") (pin "1@2") (pinfunction "P_1@2") (pintype "passive"))
    )
    (net (code "16") (name "K15") (class "Default")
      (node (ref "M1") (pin "5") (pinfunction "F_5") (pintype "bidirectional"))
      (node (ref "R15") (pin "1") (pinfunction "1_1") (pintype "passive"))
      (node (ref "SW_G") (pin "1@1") (pinfunction "P_1@1") (pintype "passive"))
      (node (ref "SW_G") (pin "1@2") (pinfunction "P_1@2") (pintype "passive"))
    )
    (net (code "17") (name "K16") (class "Default")
      (node (ref "M1") (pin "6") (pinfunction "G_6") (pintype "bidirectional"))
      (node (ref "R16") (pin "1") (pinfunction "1_1") (pintype "passive"))
      (node (ref "SW_H") (pin "1@1") (pinfunction "P_1@1") (pintype "passive"))
      (node (ref "SW_H") (pin "1@2") (pinfunction "P_1@2") (pintype "passive"))
    )
    (net (code "18") (name "K17") (class "Default")
      (node (ref "M1") (pin "7") (pinfunction "H_7") (pintype "bidirectional"))
      (node (ref "R17") (pin "1") (pinfunction "1_1") (pintype "passive"))
      (node (ref "SW_J") (pin "1@1") (pinfunction "P_1@1") (pintype "passive"))
      (node (ref "SW_J") (pin "1@2") (pinfunction "P_1@2") (pintype "passive"))
    )
    (net (code "19") (name "K20") (class "Default")
      (node (ref "M2") (pin "15") (pinfunction "A_15") (pintype "bidirectional"))
      (node (ref "R18") (pin "2") (pinfunction "2_2") (pintype "passive"))
      (node (ref "SW_I") (pin "1@1") (pinfunction "P_1@1") (pintype "passive"))
      (node (ref "SW_I") (pin "1@2") (pinfunction "P_1@2") (pintype "passive"))
    )
    (net (code "20") (name "K21") (class "Default")
      (node (ref "M2") (pin "1") (pinfunction "B_1") (pintype "bidirectional"))
      (node (ref "R19") (pin "2") (pinfunction "2_2") (pintype "passive"))
      (node (ref "SW_O") (pin "1@1") (pinfunction "P_1@1") (pintype "passive"))
      (node (ref "SW_O") (pin "1@2") (pinfunction "P_1@2") (pintype "passive"))
    )
    (net (code "21") (name "K22") (class "Default")
      (node (ref "M2") (pin "2") (pinfunction "C_2") (pintype "bidirectional"))
      (node (ref "R20") (pin "2") (pinfunction "2_2") (pintype "passive"))
      (node (ref "SW_P") (pin "1@1") (pinfunction "P_1@1") (pintype "passive"))
      (node (ref "SW_P") (pin "1@2") (pinfunction "P_1@2") (pintype "passive"))
    )
    (net (code "22") (name "K23") (class "Default")
      (node (ref "M2") (pin "3") (pinfunction "D_3") (pintype "bidirectional"))
      (node (ref "R21") (pin "2") (pinfunction "2_2") (pintype "passive"))
      (node (ref "SW_BSP") (pin "1@1") (pinfunction "P_1@1") (pintype "passive"))
      (node (ref "SW_BSP") (pin "1@2") (pinfunction "P_1@2") (pintype "passive"))
    )
    (net (code "23") (name "K24") (class "Default")
      (node (ref "M2") (pin "4") (pinfunction "E_4") (pintype "bidirectional"))
      (node (ref "R22") (pin "1") (pinfunction "1_1") (pintype "passive"))
      (node (ref "SW_K") (pin "1@1") (pinfunction "P_1@1") (pintype "passive"))
      (node (ref "SW_K") (pin "1@2") (pinfunction "P_1@2") (pintype "passive"))
    )
    (net (code "24") (name "K25") (class "Default")
      (node (ref "M2") (pin "5") (pinfunction "F_5") (pintype "bidirectional"))
      (node (ref "R23") (pin "1") (pinfunction "1_1") (pintype "passive"))
      (node (ref "SW_L") (pin "1@1") (pinfunction "P_1@1") (pintype "passive"))
      (node (ref "SW_L") (pin "1@2") (pinfunction "P_1@2") (pintype "passive"))
    )
    (net (code "25") (name "K26") (class "Default")
      (node (ref "M2") (pin "6") (pinfunction "G_6") (pintype "bidirectional"))
      (node (ref "R24") (pin "1") (pinfunction "1_1") (pintype "passive"))
      (node (ref "SW_ENT") (pin "1@1") (pinfunction "P_1@1") (pintype "passive"))
      (node (ref "SW_ENT") (pin "1@2") (pinfunction "P_1@2") (pintype "passive"))
    )
    (net (code "26") (name "K30") (class "Default")
      (node (ref "M3") (pin "15") (pinfunction "A_15") (pintype "bidirectional"))
      (node (ref "R26") (pin "2") (pinfunction "2_2") (pintype "passive"))
      (node (ref "SW_LS") (pin "1@1") (pinfunction "P_1@1") (pintype "passive"))
      (node (ref "SW_LS") (pin "1@2") (pinfunction "P_1@2") (pintype "passive"))
    )
    (net (code "27") (name "K31") (class "Default")
      (node (ref "M3") (pin "1") (pinfunction "B_1") (pintype "bidirectional"))
      (node (ref "R27") (pin "2") (pinfunction "2_2") (pintype "passive"))
      (node (ref "SW_Z") (pin "1@1") (pinfunction "P_1@1") (pintype "passive"))
      (node (ref "SW_Z") (pin "1@2") (pinfunction "P_1@2") (pintype "passive"))
    )
    (net (code "28") (name "K32") (class "Default")
      (node (ref "M3") (pin "2") (pinfunction "C_2") (pintype "bidirectional"))
      (node (ref "R28") (pin "2") (pinfunction "2_2") (pintype "passive"))
      (node (ref "SW_X") (pin "1@1") (pinfunction "P_1@1") (pintype "passive"))
      (node (ref "SW_X") (pin "1@2") (pinfunction "P_1@2") (pintype "passive"))
    )
    (net (code "29") (name "K34") (class "Default")
      (node (ref "M3") (pin "4") (pinfunction "E_4") (pintype "bidirectional"))
      (node (ref "R30") (pin "1") (pinfunction "1_1") (pintype "passive"))
      (node (ref "SW_LC") (pin "1@1") (pinfunction "P_1@1") (pintype "passive"))
      (node (ref "SW_LC") (pin "1@2") (pinfunction "P_1@2") (pintype "passive"))
    )
    (net (code "30") (name "K35") (class "Default")
      (node (ref "M3") (pin "5") (pinfunction "F_5") (pintype "bidirectional"))
      (node (ref "R31") (pin "1") (pinfunction "1_1") (pintype "passive"))
      (node (ref "SW_LW") (pin "1@1") (pinfunction "P_1@1") (pintype "passive"))
      (node (ref "SW_LW") (pin "1@2") (pinfunction "P_1@2") (pintype "passive"))
    )
    (net (code "31") (name "K36") (class "Default")
      (node (ref "M3") (pin "6") (pinfunction "G_6") (pintype "bidirectional"))
      (node (ref "R32") (pin "1") (pinfunction "1_1") (pintype "passive"))
      (node (ref "SW_LA") (pin "1@1") (pinfunction "P_1@1") (pintype "passive"))
      (node (ref "SW_LA") (pin "1@2") (pinfunction "P_1@2") (pintype "passive"))
    )
    (net (code "32") (name "K40") (class "Default")
      (node (ref "M4") (pin "15") (pinfunction "A_15") (pintype "bidirectional"))
      (node (ref "R34") (pin "2") (pinfunction "2_2") (pintype "passive"))
      (node (ref "SW_C") (pin "1@1") (pinfunction "P_1@1") (pintype "passive"))
      (node (ref "SW_C") (pin "1@2") (pinfunction "P_1@2") (pintype "passive"))
    )
    (net (code "33") (name "K41") (class "Default")
      (node (ref "M4") (pin "1") (pinfunction "B_1") (pintype "bidirectional"))
      (node (ref "R35") (pin "2") (pinfunction "2_2") (pintype "passive"))
      (node (ref "SW_V") (pin "1@1") (pinfunction "P_1@1") (pintype "passive"))
      (node (ref "SW_V") (pin "1@2") (pinfunction "P_1@2") (pintype "passive"))
    )
    (net (code "34") (name "K42") (class "Default")
      (node (ref "M4") (pin "2") (pinfunction "C_2") (pintype "bidirectional"))
      (node (ref "R36") (pin "2") (pinfunction "2_2") (pintype "passive"))
      (node (ref "SW_B") (pin "1@1") (pinfunction "P_1@1") (pintype "passive"))
      (node (ref "SW_B") (pin "1@2") (pinfunction "P_1@2") (pintype "passive"))
    )
    (net (code "35") (name "K43") (class "Default")
      (node (ref "M4") (pin "3") (pinfunction "D_3") (pintype "bidirectional"))
      (node (ref "R37") (pin "2") (pinfunction "2_2") (pintype "passive"))
      (node (ref "SW_N") (pin "1@1") (pinfunction "P_1@1") (pintype "passive"))
      (node (ref "SW_N") (pin "1@2") (pinfunction "P_1@2") (pintype "passive"))
    )
    (net (code "36") (name "K44") (class "Default")
      (node (ref "M4") (pin "4") (pinfunction "E_4") (pintype "bidirectional"))
      (node (ref "R38") (pin "1") (pinfunction "1_1") (pintype "passive"))
      (node (ref "SW_SPC_1") (pin "1@1") (pinfunction "P_1@1") (pintype "passive"))
      (node (ref "SW_SPC_1") (pin "1@2") (pinfunction "P_1@2") (pintype "passive"))
    )
    (net (code "37") (name "K45") (class "Default")
      (node (ref "M4") (pin "5") (pinfunction "F_5") (pintype "bidirectional"))
      (node (ref "R39") (pin "1") (pinfunction "1_1") (pintype "passive"))
      (node (ref "SW_SPC_2") (pin "1@1") (pinfunction "P_1@1") (pintype "passive"))
      (node (ref "SW_SPC_2") (pin "1@2") (pinfunction "P_1@2") (pintype "passive"))
    )
    (net (code "38") (name "K50") (class "Default")
      (node (ref "M5") (pin "15") (pinfunction "A_15") (pintype "bidirectional"))
      (node (ref "R42") (pin "2") (pinfunction "2_2") (pintype "passive"))
      (node (ref "SW_M") (pin "1@1") (pinfunction "P_1@1") (pintype "passive"))
      (node (ref "SW_M") (pin "1@2") (pinfunction "P_1@2") (pintype "passive"))
    )
    (net (code "39") (name "K51") (class "Default")
      (node (ref "M5") (pin "1") (pinfunction "B_1") (pintype "bidirectional"))
      (node (ref "R43") (pin "2") (pinfunction "2_2") (pintype "passive"))
      (node (ref "SW_RS") (pin "1@1") (pinfunction "P_1@1") (pintype "passive"))
      (node (ref "SW_RS") (pin "1@2") (pinfunction "P_1@2") (pintype "passive"))
    )
    (net (code "40") (name "K52") (class "Default")
      (node (ref "M5") (pin "2") (pinfunction "C_2") (pintype "bidirectional"))
      (node (ref "R44") (pin "2") (pinfunction "2_2") (pintype "passive"))
      (node (ref "SW_UP") (pin "1@1") (pinfunction "P_1@1") (pintype "passive"))
      (node (ref "SW_UP") (pin "1@2") (pinfunction "P_1@2") (pintype "passive"))
    )
    (net (code "41") (name "K53") (class "Default")
      (node (ref "M5") (pin "3") (pinfunction "D_3") (pintype "bidirectional"))
      (node (ref "R45") (pin "2") (pinfunction "2_2") (pintype "passive"))
      (node (ref "SW_DEL") (pin "1@1") (pinfunction "P_1@1") (pintype "passive"))
      (node (ref "SW_DEL") (pin "1@2") (pinfunction "P_1@2") (pintype "passive"))
    )
    (net (code "42") (name "K54") (class "Default")
      (node (ref "M5") (pin "4") (pinfunction "E_4") (pintype "bidirectional"))
      (node (ref "R46") (pin "1") (pinfunction "1_1") (pintype "passive"))
      (node (ref "SW_LF") (pin "1@1") (pinfunction "P_1@1") (pintype "passive"))
      (node (ref "SW_LF") (pin "1@2") (pinfunction "P_1@2") (pintype "passive"))
    )
    (net (code "43") (name "K55") (class "Default")
      (node (ref "M5") (pin "5") (pinfunction "F_5") (pintype "bidirectional"))
      (node (ref "R47") (pin "1") (pinfunction "1_1") (pintype "passive"))
      (node (ref "SW_DN") (pin "1@1") (pinfunction "P_1@1") (pintype "passive"))
      (node (ref "SW_DN") (pin "1@2") (pinfunction "P_1@2") (pintype "passive"))
    )
    (net (code "44") (name "K56") (class "Default")
      (node (ref "M5") (pin "6") (pinfunction "G_6") (pintype "bidirectional"))
      (node (ref "R48") (pin "1") (pinfunction "1_1") (pintype "passive"))
      (node (ref "SW_RT") (pin "1@1") (pinfunction "P_1@1") (pintype "passive"))
      (node (ref "SW_RT") (pin "1@2") (pinfunction "P_1@2") (pintype "passive"))
    )
    (net (code "45") (name "LATCH_MTX") (class "Default")
      (node (ref "M0") (pin "12") (pinfunction "LATCH_12") (pintype "bidirectional"))
      (node (ref "M0") (pin "13") (pinfunction "SS/~{PL}_13") (pintype "bidirectional"))
      (node (ref "M1") (pin "12") (pinfunction "LATCH_12") (pintype "bidirectional"))
      (node (ref "M1") (pin "13") (pinfunction "SS/~{PL}_13") (pintype "bidirectional"))
      (node (ref "M2") (pin "12") (pinfunction "LATCH_12") (pintype "bidirectional"))
      (node (ref "M2") (pin "13") (pinfunction "SS/~{PL}_13") (pintype "bidirectional"))
      (node (ref "M3") (pin "12") (pinfunction "LATCH_12") (pintype "bidirectional"))
      (node (ref "M3") (pin "13") (pinfunction "SS/~{PL}_13") (pintype "bidirectional"))
      (node (ref "M4") (pin "12") (pinfunction "LATCH_12") (pintype "bidirectional"))
      (node (ref "M4") (pin "13") (pinfunction "SS/~{PL}_13") (pintype "bidirectional"))
      (node (ref "M5") (pin "12") (pinfunction "LATCH_12") (pintype "bidirectional"))
      (node (ref "M5") (pin "13") (pinfunction "SS/~{PL}_13") (pintype "bidirectional"))
      (node (ref "R1") (pin "1") (pinfunction "1_1") (pintype "passive"))
      (node (ref "U1") (pin "3") (pinfunction "2_3") (pintype "passive"))
    )
    (net (code "46") (name "MATRIX_0_1") (class "Default")
      (node (ref "M0") (pin "14") (pinfunction "SA_14") (pintype "bidirectional"))
      (node (ref "M1") (pin "9") (pinfunction "QH_9") (pintype "bidirectional"))
    )
    (net (code "47") (name "MATRIX_1_2") (class "Default")
      (node (ref "M1") (pin "14") (pinfunction "SA_14") (pintype "bidirectional"))
      (node (ref "M2") (pin "9") (pinfunction "QH_9") (pintype "bidirectional"))
    )
    (net (code "48") (name "MATRIX_2_3") (class "Default")
      (node (ref "M2") (pin "14") (pinfunction "SA_14") (pintype "bidirectional"))
      (node (ref "M3") (pin "9") (pinfunction "QH_9") (pintype "bidirectional"))
    )
    (net (code "49") (name "MATRIX_3_4") (class "Default")
      (node (ref "M3") (pin "14") (pinfunction "SA_14") (pintype "bidirectional"))
      (node (ref "M4") (pin "9") (pinfunction "QH_9") (pintype "bidirectional"))
    )
    (net (code "50") (name "MATRIX_4_5") (class "Default")
      (node (ref "M4") (pin "14") (pinfunction "SA_14") (pintype "bidirectional"))
      (node (ref "M5") (pin "9") (pinfunction "QH_9") (pintype "bidirectional"))
    )
    (net (code "51") (name "MISO") (class "Default")
      (node (ref "KB_MATRIX") (pin "4") (pinfunction "4_4") (pintype "power_in"))
      (node (ref "M0") (pin "9") (pinfunction "QH_9") (pintype "bidirectional"))
    )
    (net (code "52") (name "MOSI") (class "Default")
      (node (ref "KB_MATRIX") (pin "3") (pinfunction "3_3") (pintype "passive"))
    )
    (net (code "53") (name "Net-(A1-2_DOUT)") (class "Default")
      (node (ref "A1") (pin "2-DOUT") (pinfunction "2_DOUT_2-DOUT") (pintype "output"))
      (node (ref "A1.5") (pin "4-DIN") (pinfunction "4_DIN_4-DIN") (pintype "input"))
    )
    (net (code "54") (name "Net-(A1-4_DIN)") (class "Default")
      (node (ref "A1") (pin "4-DIN") (pinfunction "4_DIN_4-DIN") (pintype "input"))
      (node (ref "ARGB") (pin "3") (pinfunction "3_3") (pintype "passive"))
    )
    (net (code "55") (name "Net-(A1.5-2_DOUT)") (class "Default")
      (node (ref "A1.5") (pin "2-DOUT") (pinfunction "2_DOUT_2-DOUT") (pintype "output"))
      (node (ref "A2") (pin "4-DIN") (pinfunction "4_DIN_4-DIN") (pintype "input"))
    )
    (net (code "56") (name "Net-(A2-2_DOUT)") (class "Default")
      (node (ref "A2") (pin "2-DOUT") (pinfunction "2_DOUT_2-DOUT") (pintype "output"))
      (node (ref "A3") (pin "4-DIN") (pinfunction "4_DIN_4-DIN") (pintype "input"))
    )
    (net (code "57") (name "Net-(A3-2_DOUT)") (class "Default")
      (node (ref "A3") (pin "2-DOUT") (pinfunction "2_DOUT_2-DOUT") (pintype "output"))
      (node (ref "A4") (pin "4-DIN") (pinfunction "4_DIN_4-DIN") (pintype "input"))
    )
    (net (code "58") (name "Net-(A4-2_DOUT)") (class "Default")
      (node (ref "A4") (pin "2-DOUT") (pinfunction "2_DOUT_2-DOUT") (pintype "output"))
      (node (ref "A5") (pin "4-DIN") (pinfunction "4_DIN_4-DIN") (pintype "input"))
    )
    (net (code "59") (name "Net-(A5-2_DOUT)") (class "Default")
      (node (ref "A5") (pin "2-DOUT") (pinfunction "2_DOUT_2-DOUT") (pintype "output"))
      (node (ref "A6") (pin "4-DIN") (pinfunction "4_DIN_4-DIN") (pintype "input"))
    )
    (net (code "60") (name "Net-(A6-2_DOUT)") (class "Default")
      (node (ref "A6") (pin "2-DOUT") (pinfunction "2_DOUT_2-DOUT") (pintype "output"))
      (node (ref "A7") (pin "4-DIN") (pinfunction "4_DIN_4-DIN") (pintype "input"))
    )
    (net (code "61") (name "Net-(A7-2_DOUT)") (class "Default")
      (node (ref "A7") (pin "2-DOUT") (pinfunction "2_DOUT_2-DOUT") (pintype "output"))
      (node (ref "A8") (pin "4-DIN") (pinfunction "4_DIN_4-DIN") (pintype "input"))
    )
    (net (code "62") (name "Net-(A8-2_DOUT)") (class "Default")
      (node (ref "A8") (pin "2-DOUT") (pinfunction "2_DOUT_2-DOUT") (pintype "output"))
      (node (ref "A9") (pin "4-DIN") (pinfunction "4_DIN_4-DIN") (pintype "input"))
    )
    (net (code "63") (name "Net-(A10-2_DOUT)") (class "Default")
      (node (ref "A10") (pin "2-DOUT") (pinfunction "2_DOUT_2-DOUT") (pintype "output"))
      (node (ref "A11") (pin "4-DIN") (pinfunction "4_DIN_4-DIN") (pintype "input"))
    )
    (net (code "64") (name "Net-(A10-4_DIN)") (class "Default")
      (node (ref "A10") (pin "4-DIN") (pinfunction "4_DIN_4-DIN") (pintype "input"))
      (node (ref "A9") (pin "2-DOUT") (pinfunction "2_DOUT_2-DOUT") (pintype "output"))
    )
    (net (code "65") (name "Net-(A11-2_DOUT)") (class "Default")
      (node (ref "A11") (pin "2-DOUT") (pinfunction "2_DOUT_2-DOUT") (pintype "output"))
      (node (ref "A12") (pin "4-DIN") (pinfunction "4_DIN_4-DIN") (pintype "input"))
    )
    (net (code "66") (name "Net-(A12-2_DOUT)") (class "Default")
      (node (ref "A12") (pin "2-DOUT") (pinfunction "2_DOUT_2-DOUT") (pintype "output"))
      (node (ref "A13") (pin "4-DIN") (pinfunction "4_DIN_4-DIN") (pintype "input"))
    )
    (net (code "67") (name "Net-(A13-2_DOUT)") (class "Default")
      (node (ref "A13") (pin "2-DOUT") (pinfunction "2_DOUT_2-DOUT") (pintype "output"))
      (node (ref "A14") (pin "4-DIN") (pinfunction "4_DIN_4-DIN") (pintype "input"))
    )
    (net (code "68") (name "Net-(A14-2_DOUT)") (class "Default")
      (node (ref "A14") (pin "2-DOUT") (pinfunction "2_DOUT_2-DOUT") (pintype "output"))
      (node (ref "A15") (pin "4-DIN") (pinfunction "4_DIN_4-DIN") (pintype "input"))
    )
    (net (code "69") (name "Net-(A15-2_DOUT)") (class "Default")
      (node (ref "A15") (pin "2-DOUT") (pinfunction "2_DOUT_2-DOUT") (pintype "output"))
      (node (ref "A16") (pin "4-DIN") (pinfunction "4_DIN_4-DIN") (pintype "input"))
    )
    (net (code "70") (name "Net-(A16-2_DOUT)") (class "Default")
      (node (ref "A16") (pin "2-DOUT") (pinfunction "2_DOUT_2-DOUT") (pintype "output"))
      (node (ref "A17") (pin "4-DIN") (pinfunction "4_DIN_4-DIN") (pintype "input"))
    )
    (net (code "71") (name "Net-(A17-2_DOUT)") (class "Default")
      (node (ref "A17") (pin "2-DOUT") (pinfunction "2_DOUT_2-DOUT") (pintype "output"))
      (node (ref "A18") (pin "4-DIN") (pinfunction "4_DIN_4-DIN") (pintype "input"))
    )
    (net (code "72") (name "Net-(A18-2_DOUT)") (class "Default")
      (node (ref "A18") (pin "2-DOUT") (pinfunction "2_DOUT_2-DOUT") (pintype "output"))
      (node (ref "A19") (pin "4-DIN") (pinfunction "4_DIN_4-DIN") (pintype "input"))
    )
    (net (code "73") (name "Net-(A19-2_DOUT)") (class "Default")
      (node (ref "A19") (pin "2-DOUT") (pinfunction "2_DOUT_2-DOUT") (pintype "output"))
      (node (ref "A20") (pin "4-DIN") (pinfunction "4_DIN_4-DIN") (pintype "input"))
    )
    (net (code "74") (name "Net-(A20-2_DOUT)") (class "Default")
      (node (ref "A20") (pin "2-DOUT") (pinfunction "2_DOUT_2-DOUT") (pintype "output"))
      (node (ref "A21") (pin "4-DIN") (pinfunction "4_DIN_4-DIN") (pintype "input"))
    )
    (net (code "75") (name "Net-(A21-2_DOUT)") (class "Default")
      (node (ref "A21") (pin "2-DOUT") (pinfunction "2_DOUT_2-DOUT") (pintype "output"))
      (node (ref "A22") (pin "4-DIN") (pinfunction "4_DIN_4-DIN") (pintype "input"))
    )
    (net (code "76") (name "Net-(A22-2_DOUT)") (class "Default")
      (node (ref "A22") (pin "2-DOUT") (pinfunction "2_DOUT_2-DOUT") (pintype "output"))
      (node (ref "A23") (pin "4-DIN") (pinfunction "4_DIN_4-DIN") (pintype "input"))
    )
    (net (code "77") (name "Net-(A23-2_DOUT)") (class "Default")
      (node (ref "A23") (pin "2-DOUT") (pinfunction "2_DOUT_2-DOUT") (pintype "output"))
      (node (ref "A24") (pin "4-DIN") (pinfunction "4_DIN_4-DIN") (pintype "input"))
    )
    (net (code "78") (name "Net-(A24-2_DOUT)") (class "Default")
      (node (ref "A24") (pin "2-DOUT") (pinfunction "2_DOUT_2-DOUT") (pintype "output"))
      (node (ref "A25") (pin "4-DIN") (pinfunction "4_DIN_4-DIN") (pintype "input"))
    )
    (net (code "79") (name "Net-(A25-2_DOUT)") (class "Default")
      (node (ref "A25") (pin "2-DOUT") (pinfunction "2_DOUT_2-DOUT") (pintype "output"))
      (node (ref "A26") (pin "4-DIN") (pinfunction "4_DIN_4-DIN") (pintype "input"))
    )
    (net (code "80") (name "Net-(A26-2_DOUT)") (class "Default")
      (node (ref "A26") (pin "2-DOUT") (pinfunction "2_DOUT_2-DOUT") (pintype "output"))
      (node (ref "A27") (pin "4-DIN") (pinfunction "4_DIN_4-DIN") (pintype "input"))
    )
    (net (code "81") (name "Net-(A27-2_DOUT)") (class "Default")
      (node (ref "A27") (pin "2-DOUT") (pinfunction "2_DOUT_2-DOUT") (pintype "output"))
      (node (ref "A28") (pin "4-DIN") (pinfunction "4_DIN_4-DIN") (pintype "input"))
    )
    (net (code "82") (name "Net-(A28-2_DOUT)") (class "Default")
      (node (ref "A28") (pin "2-DOUT") (pinfunction "2_DOUT_2-DOUT") (pintype "output"))
      (node (ref "A29") (pin "4-DIN") (pinfunction "4_DIN_4-DIN") (pintype "input"))
    )
    (net (code "83") (name "Net-(A29-2_DOUT)") (class "Default")
      (node (ref "A29") (pin "2-DOUT") (pinfunction "2_DOUT_2-DOUT") (pintype "output"))
      (node (ref "A30") (pin "4-DIN") (pinfunction "4_DIN_4-DIN") (pintype "input"))
    )
    (net (code "84") (name "Net-(A30-2_DOUT)") (class "Default")
      (node (ref "A30") (pin "2-DOUT") (pinfunction "2_DOUT_2-DOUT") (pintype "output"))
      (node (ref "A31") (pin "4-DIN") (pinfunction "4_DIN_4-DIN") (pintype "input"))
    )
    (net (code "85") (name "Net-(A31-2_DOUT)") (class "Default")
      (node (ref "A31") (pin "2-DOUT") (pinfunction "2_DOUT_2-DOUT") (pintype "output"))
      (node (ref "A32") (pin "4-DIN") (pinfunction "4_DIN_4-DIN") (pintype "input"))
    )
    (net (code "86") (name "Net-(A32-2_DOUT)") (class "Default")
      (node (ref "A32") (pin "2-DOUT") (pinfunction "2_DOUT_2-DOUT") (pintype "output"))
      (node (ref "A33") (pin "4-DIN") (pinfunction "4_DIN_4-DIN") (pintype "input"))
    )
    (net (code "87") (name "Net-(A33-2_DOUT)") (class "Default")
      (node (ref "A33") (pin "2-DOUT") (pinfunction "2_DOUT_2-DOUT") (pintype "output"))
      (node (ref "A34") (pin "4-DIN") (pinfunction "4_DIN_4-DIN") (pintype "input"))
    )
    (net (code "88") (name "Net-(A34-2_DOUT)") (class "Default")
      (node (ref "A34") (pin "2-DOUT") (pinfunction "2_DOUT_2-DOUT") (pintype "output"))
      (node (ref "A35") (pin "4-DIN") (pinfunction "4_DIN_4-DIN") (pintype "input"))
    )
    (net (code "89") (name "Net-(A35-2_DOUT)") (class "Default")
      (node (ref "A35") (pin "2-DOUT") (pinfunction "2_DOUT_2-DOUT") (pintype "output"))
      (node (ref "A36") (pin "4-DIN") (pinfunction "4_DIN_4-DIN") (pintype "input"))
    )
    (net (code "90") (name "Net-(A36-2_DOUT)") (class "Default")
      (node (ref "A36") (pin "2-DOUT") (pinfunction "2_DOUT_2-DOUT") (pintype "output"))
      (node (ref "A37") (pin "4-DIN") (pinfunction "4_DIN_4-DIN") (pintype "input"))
    )
    (net (code "91") (name "Net-(A37-2_DOUT)") (class "Default")
      (node (ref "A37") (pin "2-DOUT") (pinfunction "2_DOUT_2-DOUT") (pintype "output"))
      (node (ref "A38") (pin "4-DIN") (pinfunction "4_DIN_4-DIN") (pintype "input"))
    )
    (net (code "92") (name "Net-(A38-2_DOUT)") (class "Default")
      (node (ref "A38") (pin "2-DOUT") (pinfunction "2_DOUT_2-DOUT") (pintype "output"))
      (node (ref "A39") (pin "4-DIN") (pinfunction "4_DIN_4-DIN") (pintype "input"))
    )
    (net (code "93") (name "Net-(A39-2_DOUT)") (class "Default")
      (node (ref "A39") (pin "2-DOUT") (pinfunction "2_DOUT_2-DOUT") (pintype "output"))
      (node (ref "A40") (pin "4-DIN") (pinfunction "4_DIN_4-DIN") (pintype "input"))
    )
    (net (code "94") (name "Net-(A40-2_DOUT)") (class "Default")
      (node (ref "A40") (pin "2-DOUT") (pinfunction "2_DOUT_2-DOUT") (pintype "output"))
      (node (ref "A41") (pin "4-DIN") (pinfunction "4_DIN_4-DIN") (pintype "input"))
    )
    (net (code "95") (name "Net-(A41-2_DOUT)") (class "Default")
      (node (ref "A41") (pin "2-DOUT") (pinfunction "2_DOUT_2-DOUT") (pintype "output"))
      (node (ref "A42") (pin "4-DIN") (pinfunction "4_DIN_4-DIN") (pintype "input"))
    )
    (net (code "96") (name "Net-(A42-2_DOUT)") (class "Default")
      (node (ref "A42") (pin "2-DOUT") (pinfunction "2_DOUT_2-DOUT") (pintype "output"))
      (node (ref "A43") (pin "4-DIN") (pinfunction "4_DIN_4-DIN") (pintype "input"))
    )
    (net (code "97") (name "Net-(A43-2_DOUT)") (class "Default")
      (node (ref "A43") (pin "2-DOUT") (pinfunction "2_DOUT_2-DOUT") (pintype "output"))
      (node (ref "I44") (pin "D") (pinfunction "D_D") (pintype "passive"))
    )
    (net (code "98") (name "Net-(M2-H)") (class "Default")
      (node (ref "M2") (pin "7") (pinfunction "H_7") (pintype "bidirectional"))
      (node (ref "R25") (pin "1") (pinfunction "1_1") (pintype "passive"))
    )
    (net (code "99") (name "Net-(M3-D)") (class "Default")
      (node (ref "M3") (pin "3") (pinfunction "D_3") (pintype "bidirectional"))
      (node (ref "R29") (pin "2") (pinfunction "2_2") (pintype "passive"))
    )
    (net (code "100") (name "Net-(M3-H)") (class "Default")
      (node (ref "M3") (pin "7") (pinfunction "H_7") (pintype "bidirectional"))
      (node (ref "R33") (pin "1") (pinfunction "1_1") (pintype "passive"))
    )
    (net (code "101") (name "Net-(M4-G)") (class "Default")
      (node (ref "M4") (pin "6") (pinfunction "G_6") (pintype "bidirectional"))
      (node (ref "R40") (pin "1") (pinfunction "1_1") (pintype "passive"))
    )
    (net (code "102") (name "Net-(M4-H)") (class "Default")
      (node (ref "M4") (pin "7") (pinfunction "H_7") (pintype "bidirectional"))
      (node (ref "R41") (pin "1") (pinfunction "1_1") (pintype "passive"))
    )
    (net (code "103") (name "Net-(M5-H)") (class "Default")
      (node (ref "M5") (pin "7") (pinfunction "H_7") (pintype "bidirectional"))
      (node (ref "R49") (pin "1") (pinfunction "1_1") (pintype "passive"))
    )
    (net (code "104") (name "SCK") (class "Default")
      (node (ref "KB_MATRIX") (pin "5") (pinfunction "5_5") (pintype "power_in"))
      (node (ref "M0") (pin "11") (pinfunction "SC/SCK_11") (pintype "bidirectional"))
      (node (ref "M1") (pin "11") (pinfunction "SC/SCK_11") (pintype "bidirectional"))
      (node (ref "M2") (pin "11") (pinfunction "SC/SCK_11") (pintype "bidirectional"))
      (node (ref "M3") (pin "11") (pinfunction "SC/SCK_11") (pintype "bidirectional"))
      (node (ref "M4") (pin "11") (pinfunction "SC/SCK_11") (pintype "bidirectional"))
      (node (ref "M5") (pin "11") (pinfunction "SC/SCK_11") (pintype "bidirectional"))
    )
    (net (code "105") (name "VCC_1") (class "Default")
      (node (ref "A1") (pin "1-VDD") (pinfunction "1_VDD_1-VDD") (pintype "power_in"))
      (node (ref "A1.5") (pin "1-VDD") (pinfunction "1_VDD_1-VDD") (pintype "power_in"))
      (node (ref "A10") (pin "1-VDD") (pinfunction "1_VDD_1-VDD") (pintype "power_in"))
      (node (ref "A11") (pin "1-VDD") (pinfunction "1_VDD_1-VDD") (pintype "power_in"))
      (node (ref "A12") (pin "1-VDD") (pinfunction "1_VDD_1-VDD") (pintype "power_in"))
      (node (ref "A13") (pin "1-VDD") (pinfunction "1_VDD_1-VDD") (pintype "power_in"))
      (node (ref "A14") (pin "1-VDD") (pinfunction "1_VDD_1-VDD") (pintype "power_in"))
      (node (ref "A15") (pin "1-VDD") (pinfunction "1_VDD_1-VDD") (pintype "power_in"))
      (node (ref "A16") (pin "1-VDD") (pinfunction "1_VDD_1-VDD") (pintype "power_in"))
      (node (ref "A17") (pin "1-VDD") (pinfunction "1_VDD_1-VDD") (pintype "power_in"))
      (node (ref "A18") (pin "1-VDD") (pinfunction "1_VDD_1-VDD") (pintype "power_in"))
      (node (ref "A19") (pin "1-VDD") (pinfunction "1_VDD_1-VDD") (pintype "power_in"))
      (node (ref "A2") (pin "1-VDD") (pinfunction "1_VDD_1-VDD") (pintype "power_in"))
      (node (ref "A20") (pin "1-VDD") (pinfunction "1_VDD_1-VDD") (pintype "power_in"))
      (node (ref "A21") (pin "1-VDD") (pinfunction "1_VDD_1-VDD") (pintype "power_in"))
      (node (ref "A22") (pin "1-VDD") (pinfunction "1_VDD_1-VDD") (pintype "power_in"))
      (node (ref "A23") (pin "1-VDD") (pinfunction "1_VDD_1-VDD") (pintype "power_in"))
      (node (ref "A24") (pin "1-VDD") (pinfunction "1_VDD_1-VDD") (pintype "power_in"))
      (node (ref "A25") (pin "1-VDD") (pinfunction "1_VDD_1-VDD") (pintype "power_in"))
      (node (ref "A26") (pin "1-VDD") (pinfunction "1_VDD_1-VDD") (pintype "power_in"))
      (node (ref "A27") (pin "1-VDD") (pinfunction "1_VDD_1-VDD") (pintype "power_in"))
      (node (ref "A28") (pin "1-VDD") (pinfunction "1_VDD_1-VDD") (pintype "power_in"))
      (node (ref "A29") (pin "1-VDD") (pinfunction "1_VDD_1-VDD") (pintype "power_in"))
      (node (ref "A3") (pin "1-VDD") (pinfunction "1_VDD_1-VDD") (pintype "power_in"))
      (node (ref "A30") (pin "1-VDD") (pinfunction "1_VDD_1-VDD") (pintype "power_in"))
      (node (ref "A31") (pin "1-VDD") (pinfunction "1_VDD_1-VDD") (pintype "power_in"))
      (node (ref "A32") (pin "1-VDD") (pinfunction "1_VDD_1-VDD") (pintype "power_in"))
      (node (ref "A33") (pin "1-VDD") (pinfunction "1_VDD_1-VDD") (pintype "power_in"))
      (node (ref "A34") (pin "1-VDD") (pinfunction "1_VDD_1-VDD") (pintype "power_in"))
      (node (ref "A35") (pin "1-VDD") (pinfunction "1_VDD_1-VDD") (pintype "power_in"))
      (node (ref "A36") (pin "1-VDD") (pinfunction "1_VDD_1-VDD") (pintype "power_in"))
      (node (ref "A37") (pin "1-VDD") (pinfunction "1_VDD_1-VDD") (pintype "power_in"))
      (node (ref "A38") (pin "1-VDD") (pinfunction "1_VDD_1-VDD") (pintype "power_in"))
      (node (ref "A39") (pin "1-VDD") (pinfunction "1_VDD_1-VDD") (pintype "power_in"))
      (node (ref "A4") (pin "1-VDD") (pinfunction "1_VDD_1-VDD") (pintype "power_in"))
      (node (ref "A40") (pin "1-VDD") (pinfunction "1_VDD_1-VDD") (pintype "power_in"))
      (node (ref "A41") (pin "1-VDD") (pinfunction "1_VDD_1-VDD") (pintype "power_in"))
      (node (ref "A42") (pin "1-VDD") (pinfunction "1_VDD_1-VDD") (pintype "power_in"))
      (node (ref "A43") (pin "1-VDD") (pinfunction "1_VDD_1-VDD") (pintype "power_in"))
      (node (ref "A5") (pin "1-VDD") (pinfunction "1_VDD_1-VDD") (pintype "power_in"))
      (node (ref "A6") (pin "1-VDD") (pinfunction "1_VDD_1-VDD") (pintype "power_in"))
      (node (ref "A7") (pin "1-VDD") (pinfunction "1_VDD_1-VDD") (pintype "power_in"))
      (node (ref "A8") (pin "1-VDD") (pinfunction "1_VDD_1-VDD") (pintype "power_in"))
      (node (ref "A9") (pin "1-VDD") (pinfunction "1_VDD_1-VDD") (pintype "power_in"))
      (node (ref "ARGB") (pin "2") (pinfunction "2_2") (pintype "passive"))
      (node (ref "CA1") (pin "1") (pinfunction "1_1") (pintype "passive"))
      (node (ref "CA11") (pin "1") (pinfunction "1_1") (pintype "passive"))
      (node (ref "CA13") (pin "1") (pinfunction "1_1") (pintype "passive"))
      (node (ref "CA15") (pin "1") (pinfunction "1_1") (pintype "passive"))
      (node (ref "CA17") (pin "1") (pinfunction "1_1") (pintype "passive"))
      (node (ref "CA19") (pin "1") (pinfunction "1_1") (pintype "passive"))
      (node (ref "CA21") (pin "1") (pinfunction "1_1") (pintype "passive"))
      (node (ref "CA23") (pin "1") (pinfunction "1_1") (pintype "passive"))
      (node (ref "CA25") (pin "1") (pinfunction "1_1") (pintype "passive"))
      (node (ref "CA27") (pin "1") (pinfunction "1_1") (pintype "passive"))
      (node (ref "CA29") (pin "1") (pinfunction "1_1") (pintype "passive"))
      (node (ref "CA3") (pin "1") (pinfunction "1_1") (pintype "passive"))
      (node (ref "CA31") (pin "1") (pinfunction "1_1") (pintype "passive"))
      (node (ref "CA33") (pin "1") (pinfunction "1_1") (pintype "passive"))
      (node (ref "CA35") (pin "1") (pinfunction "1_1") (pintype "passive"))
      (node (ref "CA37") (pin "1") (pinfunction "1_1") (pintype "passive"))
      (node (ref "CA39") (pin "1") (pinfunction "1_1") (pintype "passive"))
      (node (ref "CA41") (pin "1") (pinfunction "1_1") (pintype "passive"))
      (node (ref "CA43") (pin "1") (pinfunction "1_1") (pintype "passive"))
      (node (ref "CA5") (pin "1") (pinfunction "1_1") (pintype "passive"))
      (node (ref "CA6") (pin "1") (pinfunction "1_1") (pintype "passive"))
      (node (ref "CA7") (pin "1") (pinfunction "1_1") (pintype "passive"))
      (node (ref "CA9") (pin "1") (pinfunction "1_1") (pintype "passive"))
      (node (ref "I44") (pin "V") (pinfunction "V_V") (pintype "power_in"))
    )
    (net (code "106") (name "VCC_2") (class "Default")
      (node (ref "C1") (pin "1") (pinfunction "1_1") (pintype "passive"))
      (node (ref "C2") (pin "1") (pinfunction "1_1") (pintype "passive"))
      (node (ref "C3") (pin "1") (pinfunction "1_1") (pintype "passive"))
      (node (ref "C4") (pin "1") (pinfunction "1_1") (pintype "passive"))
      (node (ref "C5") (pin "1") (pinfunction "1_1") (pintype "passive"))
      (node (ref "C6") (pin "1") (pinfunction "1_1") (pintype "passive"))
      (node (ref "KB_MATRIX") (pin "2") (pinfunction "2_2") (pintype "passive"))
      (node (ref "M0") (pin "16") (pinfunction "VCC_16") (pintype "bidirectional"))
      (node (ref "M1") (pin "16") (pinfunction "VCC_16") (pintype "bidirectional"))
      (node (ref "M2") (pin "16") (pinfunction "VCC_16") (pintype "bidirectional"))
      (node (ref "M3") (pin "16") (pinfunction "VCC_16") (pintype "bidirectional"))
      (node (ref "M4") (pin "16") (pinfunction "VCC_16") (pintype "bidirectional"))
      (node (ref "M5") (pin "16") (pinfunction "VCC_16") (pintype "bidirectional"))
      (node (ref "R1") (pin "2") (pinfunction "2_2") (pintype "passive"))
      (node (ref "SW_A") (pin "2@1") (pinfunction "S_2@1") (pintype "passive"))
      (node (ref "SW_A") (pin "2@2") (pinfunction "S_2@2") (pintype "passive"))
      (node (ref "SW_B") (pin "2@1") (pinfunction "S_2@1") (pintype "passive"))
      (node (ref "SW_B") (pin "2@2") (pinfunction "S_2@2") (pintype "passive"))
      (node (ref "SW_BSP") (pin "2@1") (pinfunction "S_2@1") (pintype "passive"))
      (node (ref "SW_BSP") (pin "2@2") (pinfunction "S_2@2") (pintype "passive"))
      (node (ref "SW_C") (pin "2@1") (pinfunction "S_2@1") (pintype "passive"))
      (node (ref "SW_C") (pin "2@2") (pinfunction "S_2@2") (pintype "passive"))
      (node (ref "SW_D") (pin "2@1") (pinfunction "S_2@1") (pintype "passive"))
      (node (ref "SW_D") (pin "2@2") (pinfunction "S_2@2") (pintype "passive"))
      (node (ref "SW_DEL") (pin "2@1") (pinfunction "S_2@1") (pintype "passive"))
      (node (ref "SW_DEL") (pin "2@2") (pinfunction "S_2@2") (pintype "passive"))
      (node (ref "SW_DN") (pin "2@1") (pinfunction "S_2@1") (pintype "passive"))
      (node (ref "SW_DN") (pin "2@2") (pinfunction "S_2@2") (pintype "passive"))
      (node (ref "SW_E") (pin "2@1") (pinfunction "S_2@1") (pintype "passive"))
      (node (ref "SW_E") (pin "2@2") (pinfunction "S_2@2") (pintype "passive"))
      (node (ref "SW_ENT") (pin "2@1") (pinfunction "S_2@1") (pintype "passive"))
      (node (ref "SW_ENT") (pin "2@2") (pinfunction "S_2@2") (pintype "passive"))
      (node (ref "SW_ESC") (pin "2@1") (pinfunction "S_2@1") (pintype "passive"))
      (node (ref "SW_ESC") (pin "2@2") (pinfunction "S_2@2") (pintype "passive"))
      (node (ref "SW_F") (pin "2@1") (pinfunction "S_2@1") (pintype "passive"))
      (node (ref "SW_F") (pin "2@2") (pinfunction "S_2@2") (pintype "passive"))
      (node (ref "SW_G") (pin "2@1") (pinfunction "S_2@1") (pintype "passive"))
      (node (ref "SW_G") (pin "2@2") (pinfunction "S_2@2") (pintype "passive"))
      (node (ref "SW_H") (pin "2@1") (pinfunction "S_2@1") (pintype "passive"))
      (node (ref "SW_H") (pin "2@2") (pinfunction "S_2@2") (pintype "passive"))
      (node (ref "SW_I") (pin "2@1") (pinfunction "S_2@1") (pintype "passive"))
      (node (ref "SW_I") (pin "2@2") (pinfunction "S_2@2") (pintype "passive"))
      (node (ref "SW_J") (pin "2@1") (pinfunction "S_2@1") (pintype "passive"))
      (node (ref "SW_J") (pin "2@2") (pinfunction "S_2@2") (pintype "passive"))
      (node (ref "SW_K") (pin "2@1") (pinfunction "S_2@1") (pintype "passive"))
      (node (ref "SW_K") (pin "2@2") (pinfunction "S_2@2") (pintype "passive"))
      (node (ref "SW_L") (pin "2@1") (pinfunction "S_2@1") (pintype "passive"))
      (node (ref "SW_L") (pin "2@2") (pinfunction "S_2@2") (pintype "passive"))
      (node (ref "SW_LA") (pin "2@1") (pinfunction "S_2@1") (pintype "passive"))
      (node (ref "SW_LA") (pin "2@2") (pinfunction "S_2@2") (pintype "passive"))
      (node (ref "SW_LC") (pin "2@1") (pinfunction "S_2@1") (pintype "passive"))
      (node (ref "SW_LC") (pin "2@2") (pinfunction "S_2@2") (pintype "passive"))
      (node (ref "SW_LF") (pin "2@1") (pinfunction "S_2@1") (pintype "passive"))
      (node (ref "SW_LF") (pin "2@2") (pinfunction "S_2@2") (pintype "passive"))
      (node (ref "SW_LS") (pin "2@1") (pinfunction "S_2@1") (pintype "passive"))
      (node (ref "SW_LS") (pin "2@2") (pinfunction "S_2@2") (pintype "passive"))
      (node (ref "SW_LW") (pin "2@1") (pinfunction "S_2@1") (pintype "passive"))
      (node (ref "SW_LW") (pin "2@2") (pinfunction "S_2@2") (pintype "passive"))
      (node (ref "SW_M") (pin "2@1") (pinfunction "S_2@1") (pintype "passive"))
      (node (ref "SW_M") (pin "2@2") (pinfunction "S_2@2") (pintype "passive"))
      (node (ref "SW_N") (pin "2@1") (pinfunction "S_2@1") (pintype "passive"))
      (node (ref "SW_N") (pin "2@2") (pinfunction "S_2@2") (pintype "passive"))
      (node (ref "SW_O") (pin "2@1") (pinfunction "S_2@1") (pintype "passive"))
      (node (ref "SW_O") (pin "2@2") (pinfunction "S_2@2") (pintype "passive"))
      (node (ref "SW_P") (pin "2@1") (pinfunction "S_2@1") (pintype "passive"))
      (node (ref "SW_P") (pin "2@2") (pinfunction "S_2@2") (pintype "passive"))
      (node (ref "SW_Q") (pin "2@1") (pinfunction "S_2@1") (pintype "passive"))
      (node (ref "SW_Q") (pin "2@2") (pinfunction "S_2@2") (pintype "passive"))
      (node (ref "SW_R") (pin "2@1") (pinfunction "S_2@1") (pintype "passive"))
      (node (ref "SW_R") (pin "2@2") (pinfunction "S_2@2") (pintype "passive"))
      (node (ref "SW_RS") (pin "2@1") (pinfunction "S_2@1") (pintype "passive"))
      (node (ref "SW_RS") (pin "2@2") (pinfunction "S_2@2") (pintype "passive"))
      (node (ref "SW_RT") (pin "2@1") (pinfunction "S_2@1") (pintype "passive"))
      (node (ref "SW_RT") (pin "2@2") (pinfunction "S_2@2") (pintype "passive"))
      (node (ref "SW_S") (pin "2@1") (pinfunction "S_2@1") (pintype "passive"))
      (node (ref "SW_S") (pin "2@2") (pinfunction "S_2@2") (pintype "passive"))
      (node (ref "SW_SPC_1") (pin "2@1") (pinfunction "S_2@1") (pintype "passive"))
      (node (ref "SW_SPC_1") (pin "2@2") (pinfunction "S_2@2") (pintype "passive"))
      (node (ref "SW_SPC_2") (pin "2@1") (pinfunction "S_2@1") (pintype "passive"))
      (node (ref "SW_SPC_2") (pin "2@2") (pinfunction "S_2@2") (pintype "passive"))
      (node (ref "SW_T") (pin "2@1") (pinfunction "S_2@1") (pintype "passive"))
      (node (ref "SW_T") (pin "2@2") (pinfunction "S_2@2") (pintype "passive"))
      (node (ref "SW_TAB") (pin "2@1") (pinfunction "S_2@1") (pintype "passive"))
      (node (ref "SW_TAB") (pin "2@2") (pinfunction "S_2@2") (pintype "passive"))
      (node (ref "SW_U") (pin "2@1") (pinfunction "S_2@1") (pintype "passive"))
      (node (ref "SW_U") (pin "2@2") (pinfunction "S_2@2") (pintype "passive"))
      (node (ref "SW_UP") (pin "2@1") (pinfunction "S_2@1") (pintype "passive"))
      (node (ref "SW_UP") (pin "2@2") (pinfunction "S_2@2") (pintype "passive"))
      (node (ref "SW_V") (pin "2@1") (pinfunction "S_2@1") (pintype "passive"))
      (node (ref "SW_V") (pin "2@2") (pinfunction "S_2@2") (pintype "passive"))
      (node (ref "SW_W") (pin "2@1") (pinfunction "S_2@1") (pintype "passive"))
      (node (ref "SW_W") (pin "2@2") (pinfunction "S_2@2") (pintype "passive"))
      (node (ref "SW_X") (pin "2@1") (pinfunction "S_2@1") (pintype "passive"))
      (node (ref "SW_X") (pin "2@2") (pinfunction "S_2@2") (pintype "passive"))
      (node (ref "SW_Y") (pin "2@1") (pinfunction "S_2@1") (pintype "passive"))
      (node (ref "SW_Y") (pin "2@2") (pinfunction "S_2@2") (pintype "passive"))
      (node (ref "SW_Z") (pin "2@1") (pinfunction "S_2@1") (pintype "passive"))
      (node (ref "SW_Z") (pin "2@2") (pinfunction "S_2@2") (pintype "passive"))
    )
  )
)
